# SCH_Knov-V3_3-sound-_DMS13A_2026-08-17.net
KiCad netlist of a schematic drawn in EasyEDA
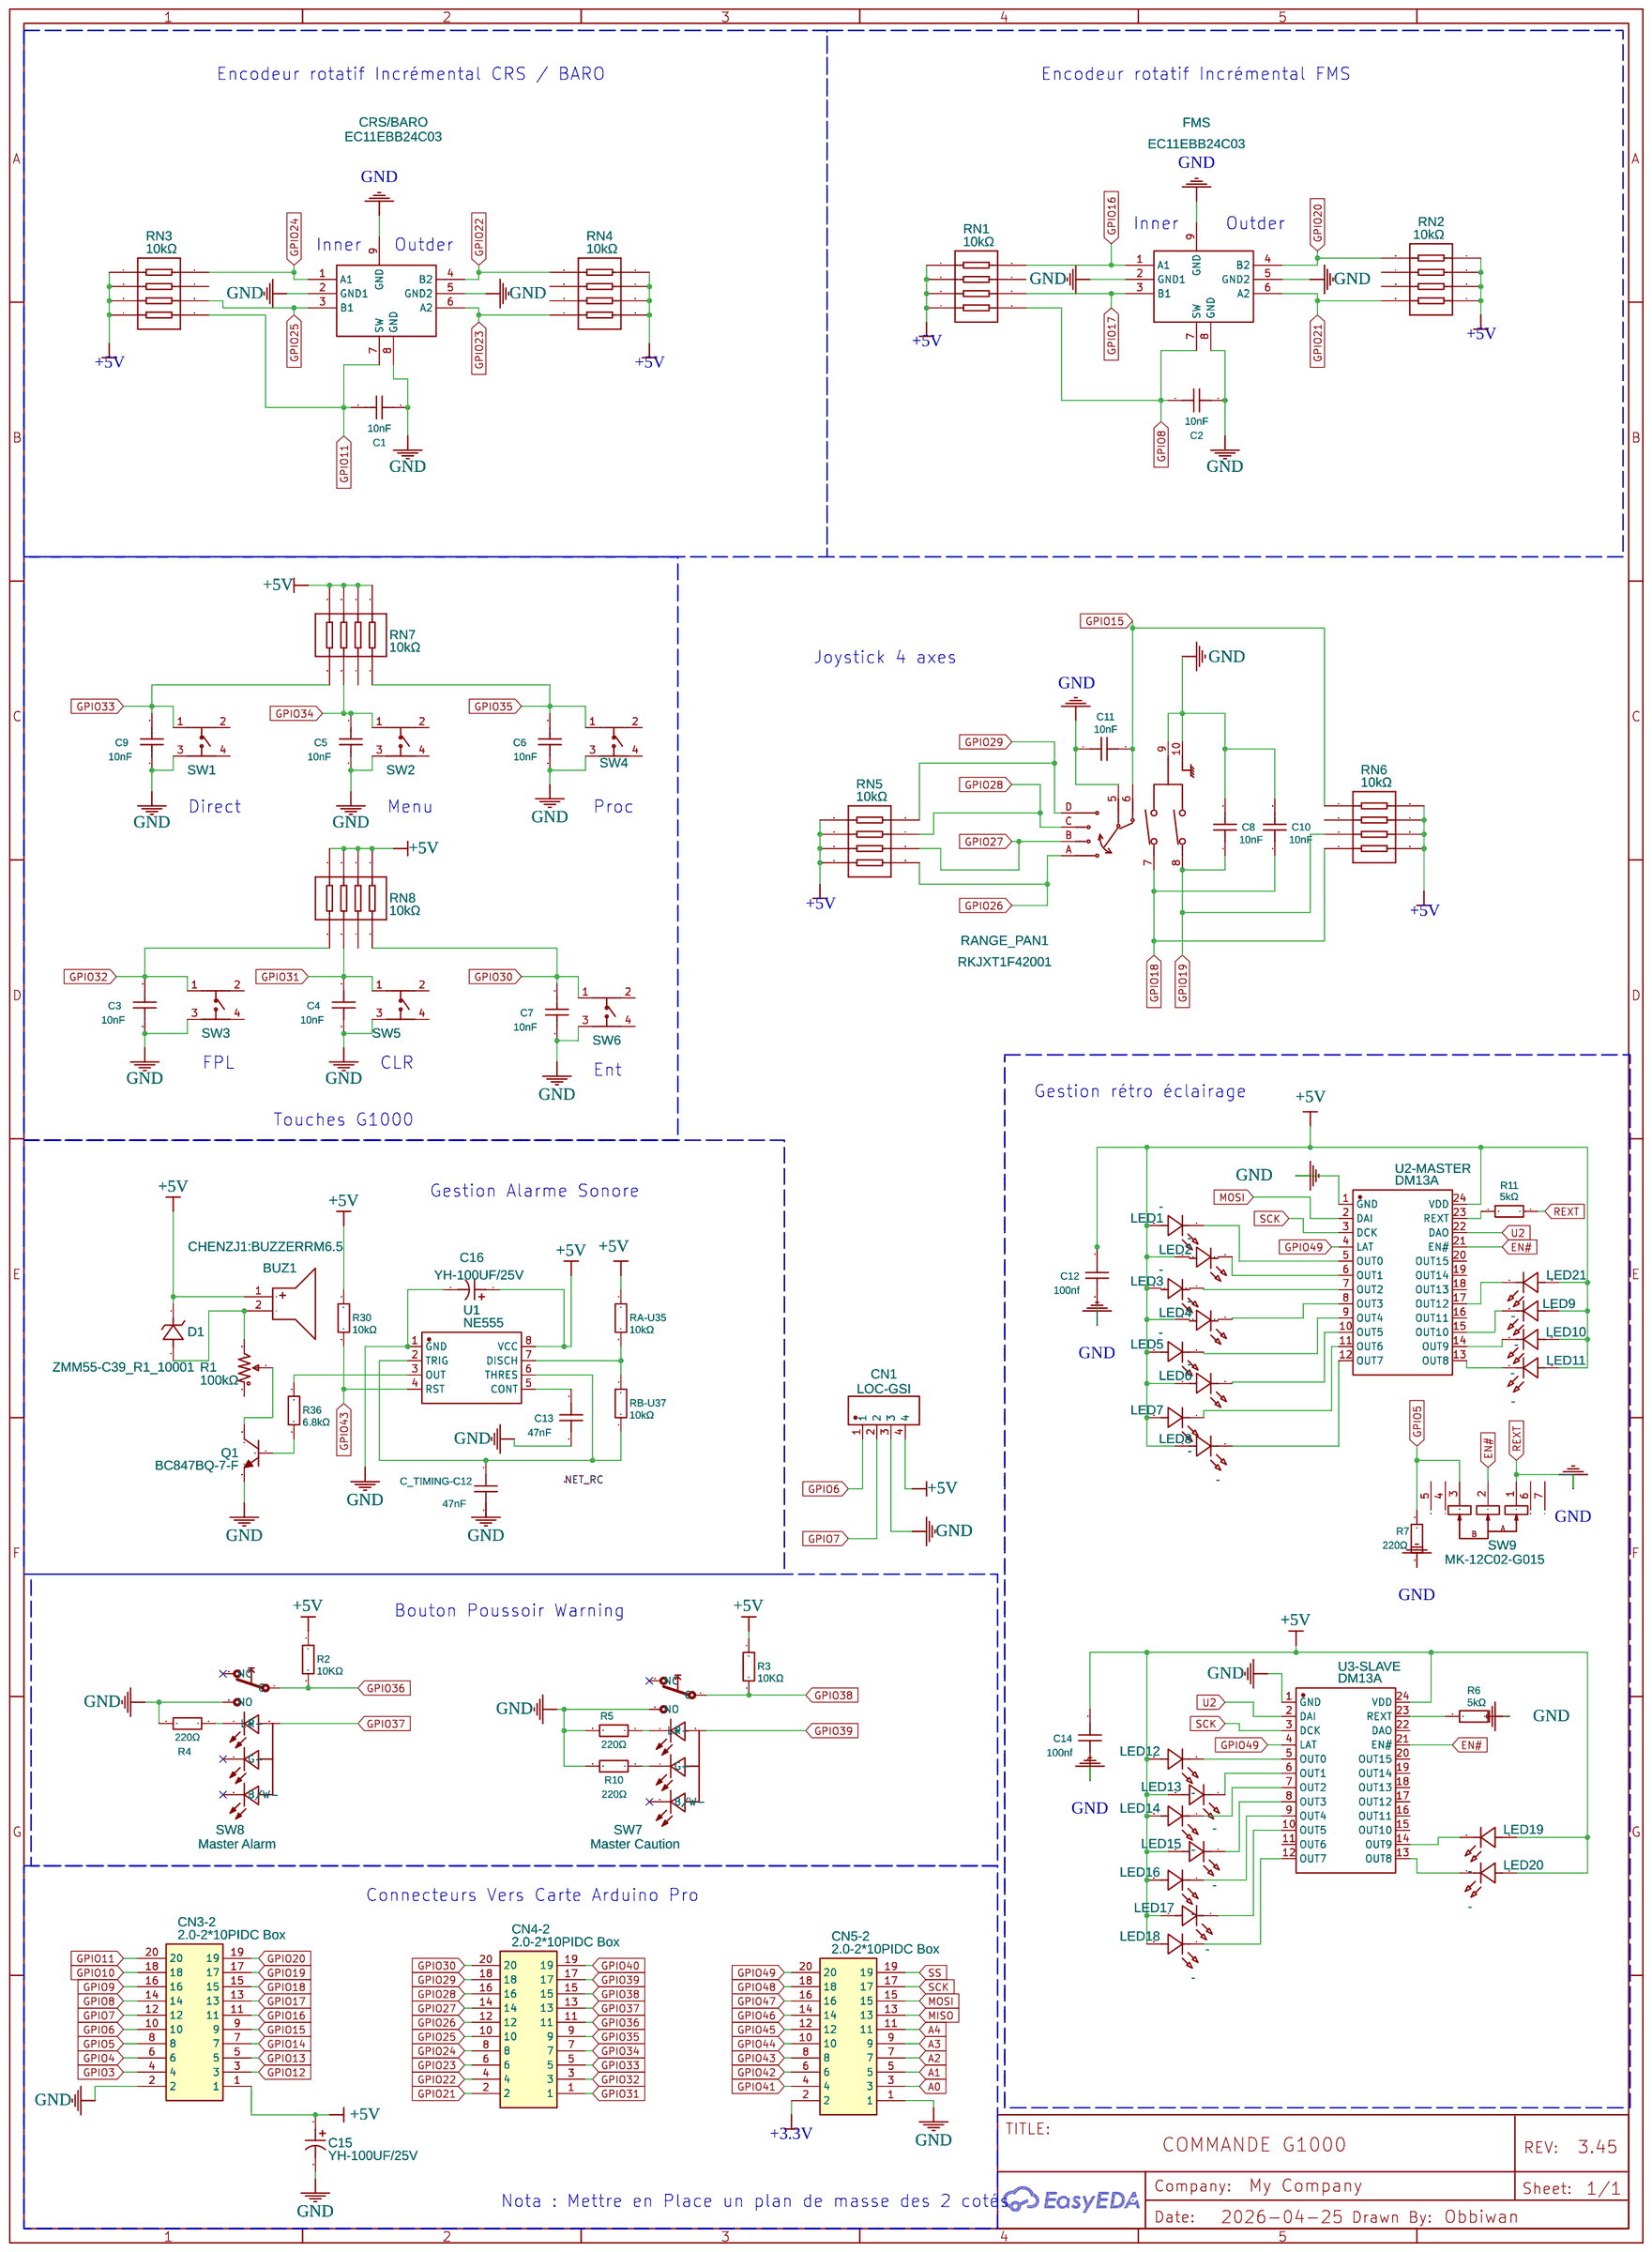
[diagram p0: Platine Bouton Sound +DMS13A]
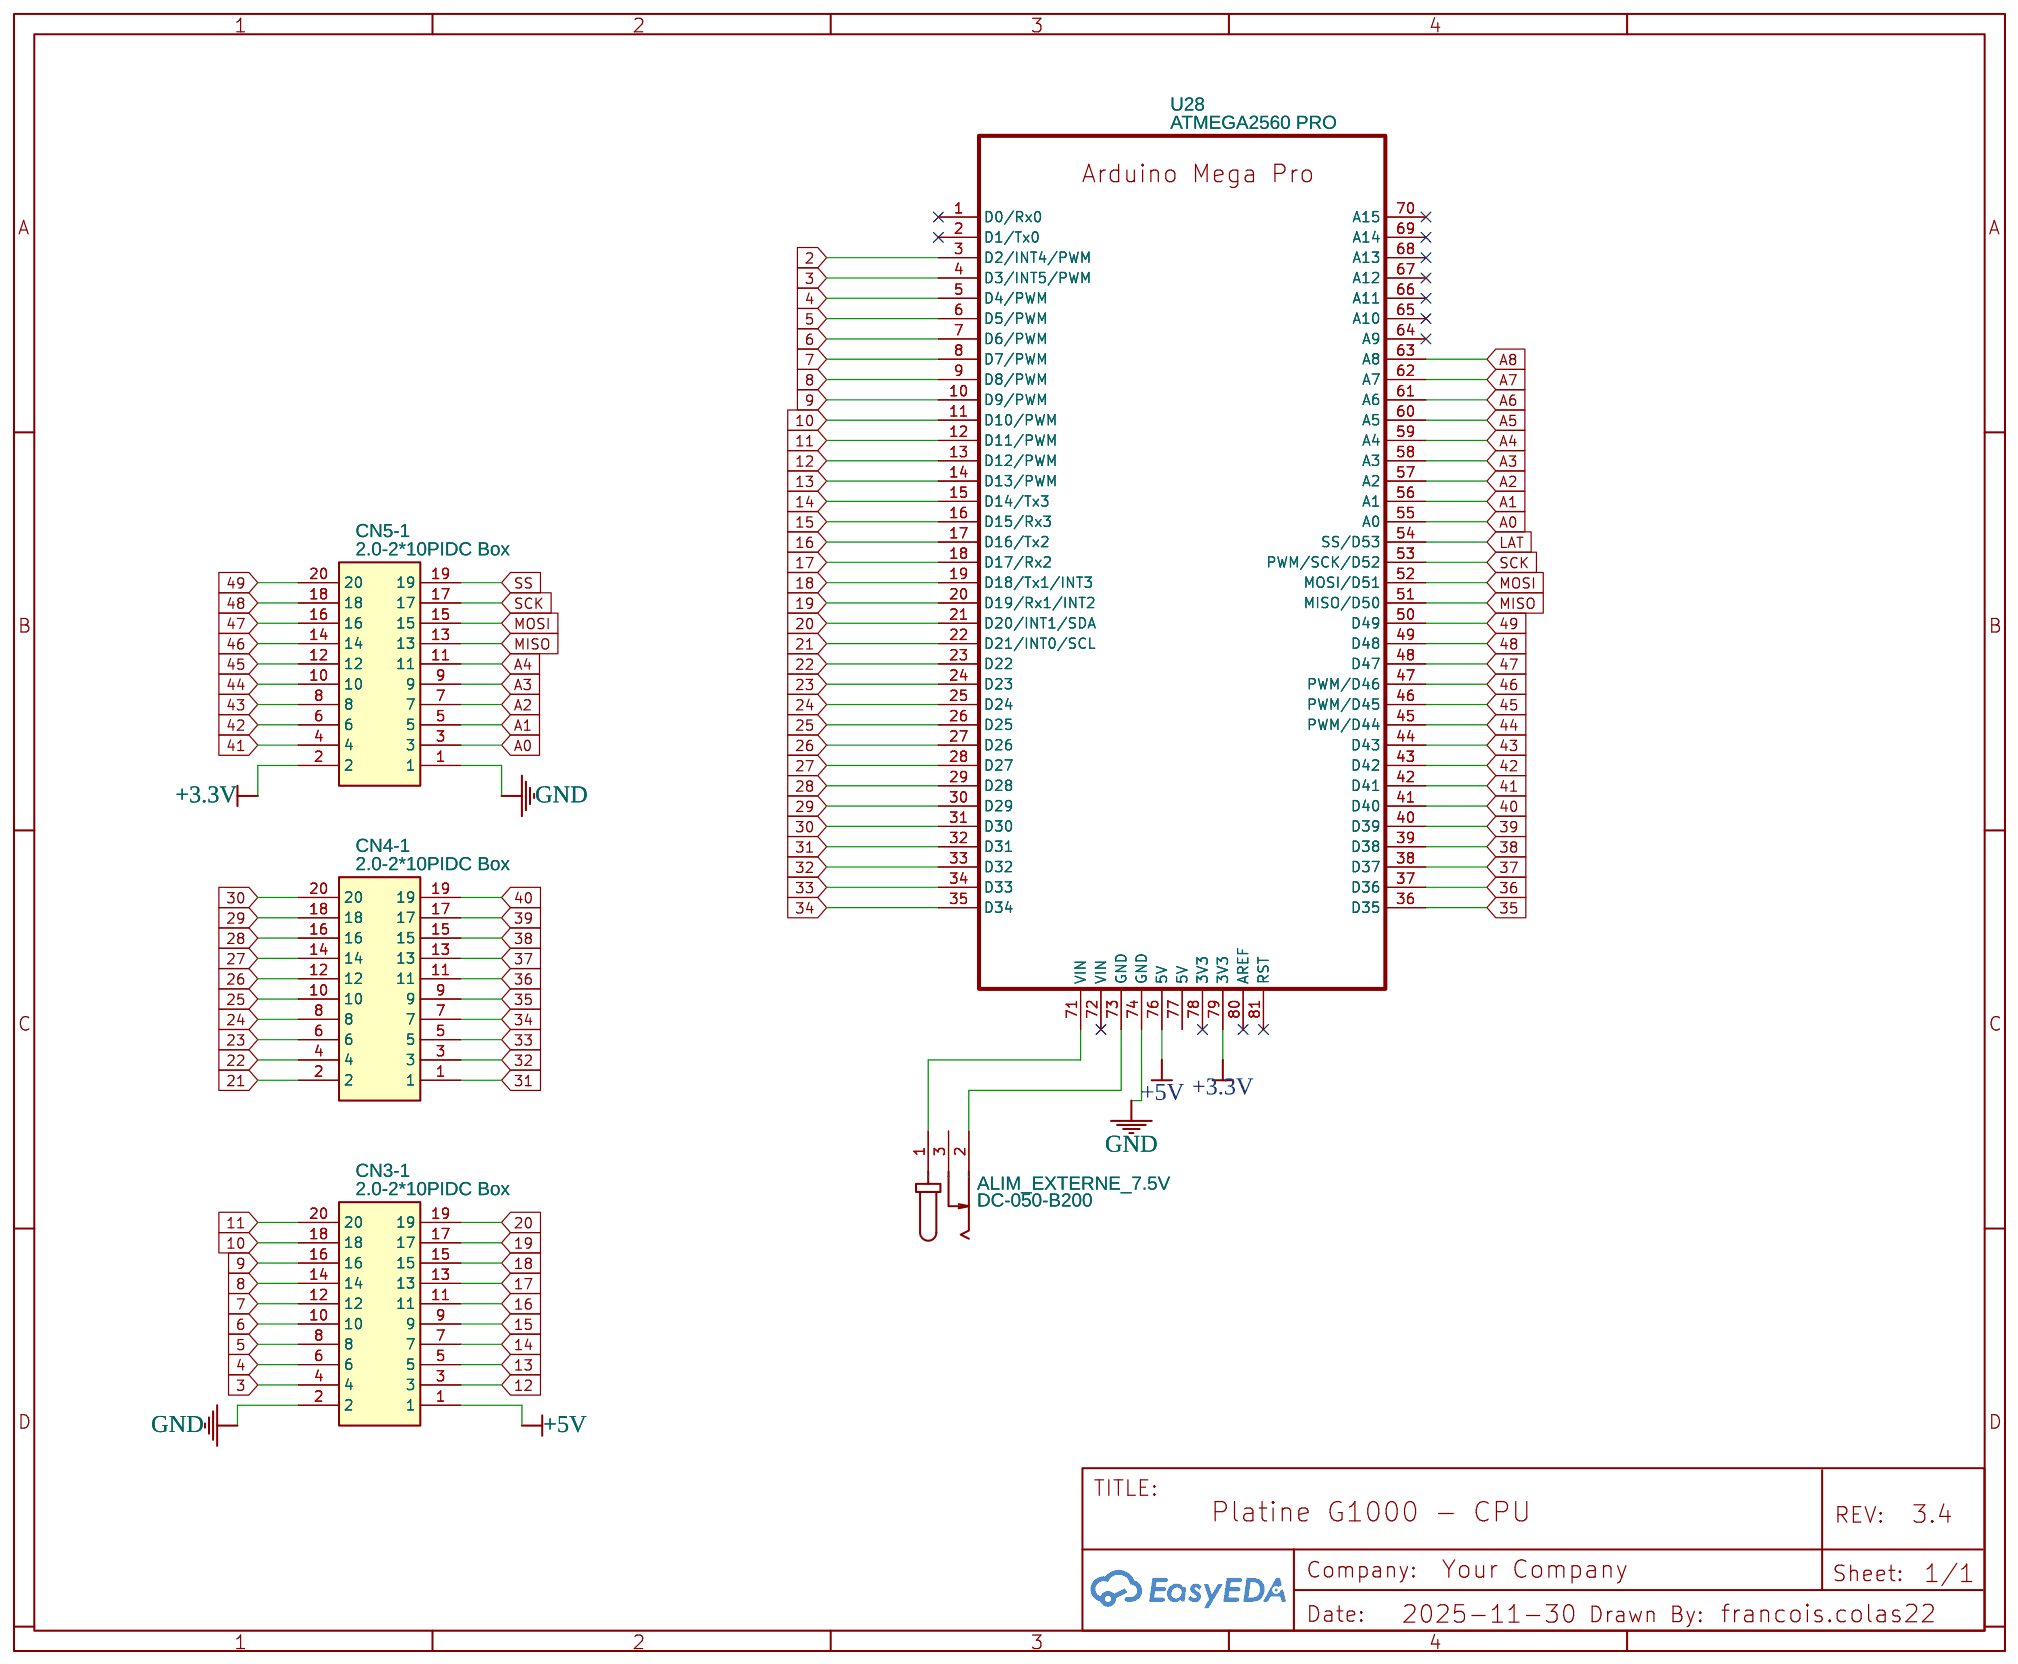
[diagram p1: Platine Arduino sound +DMS13A]
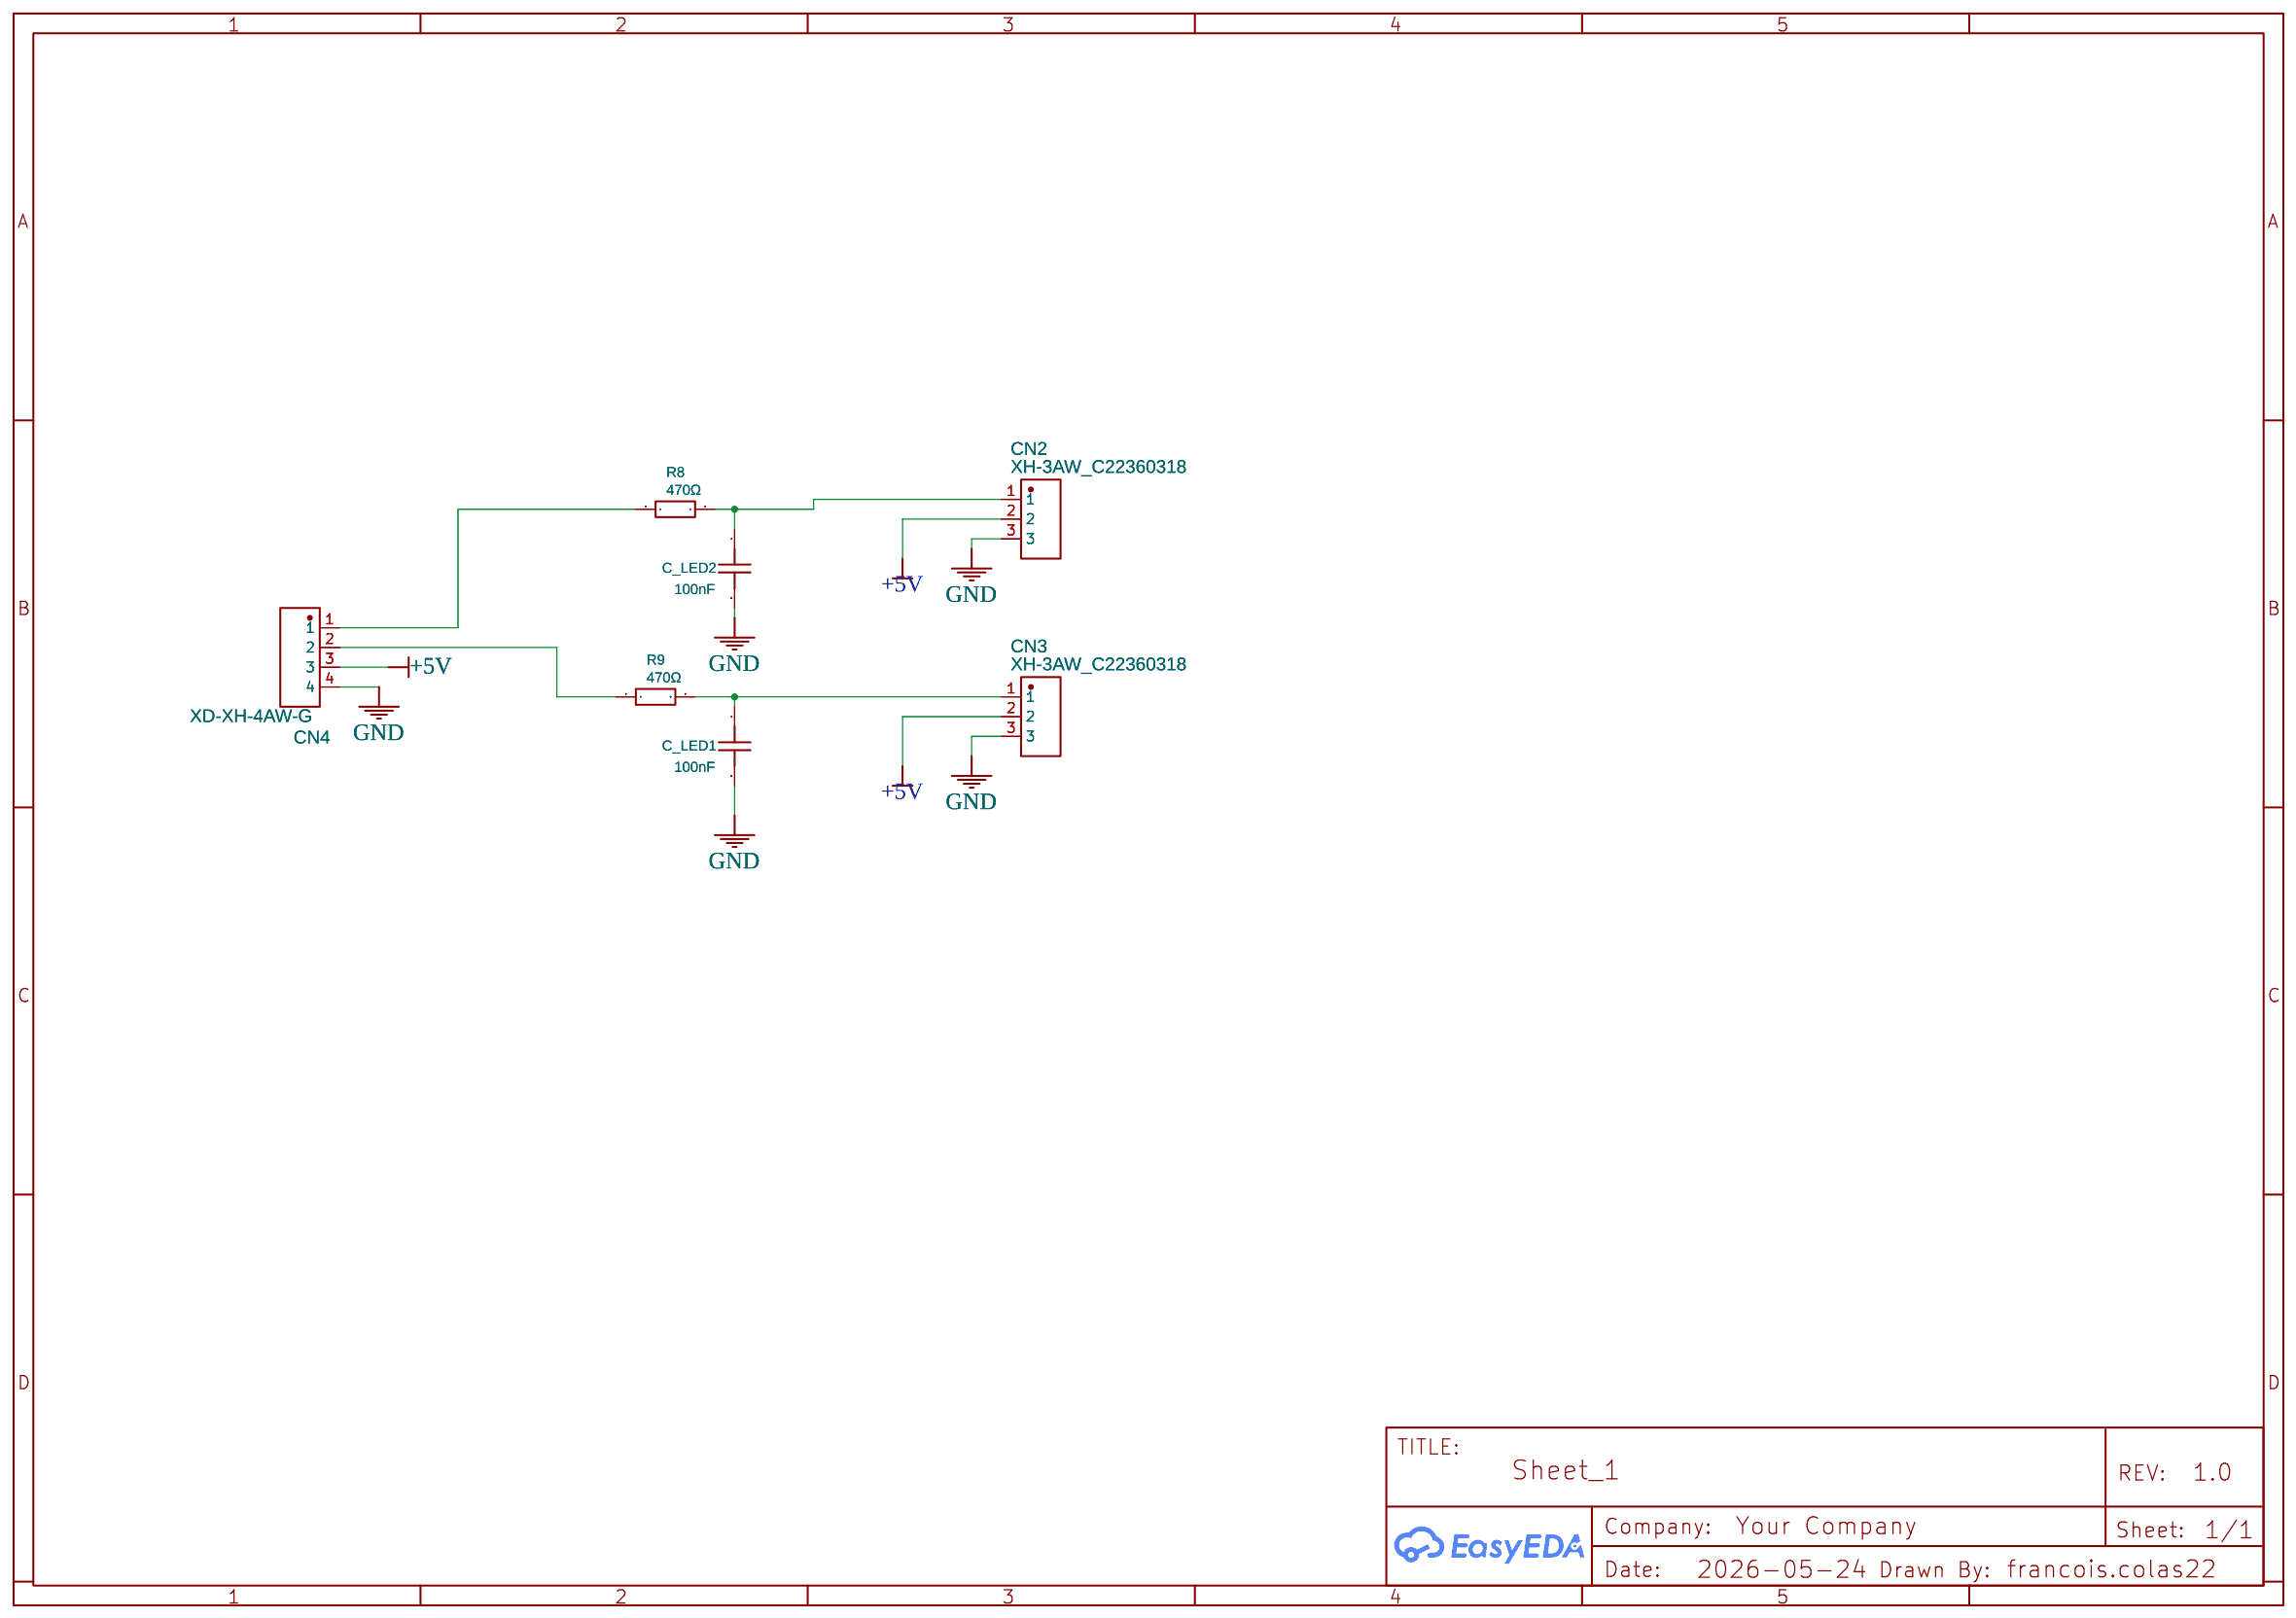
[diagram p2: Platine LED]

(export (version "E")
  (design (tool "Eeschema 10.0.6"))
  (components
    (comp (ref "BUZ1")
      (value "CHENZJ1:BUZZERRM6.5")
      (fields (field (name "Manufacturer Part") "chenzj1:Buzzer_12x9.5RM6.5"))
      (libsource (lib "") (part "CHENZJ1{colon}BUZZER_12X9.5RM6.5"))
    )
    (comp (ref "C1")
      (value "10nF")
      (fields
        (field (name "Manufacturer Part") "CT41G-0603-2X1-50V-0.01μF-K(N)")
        (field (name "Manufacturer") "TORCH(火炬)")
      )
      (libsource (lib "") (part "CT41G-0603-2X1-50V-0.01UF-K(N)"))
    )
    (comp (ref "C2")
      (value "10nF")
      (fields
        (field (name "Manufacturer Part") "CT41G-0603-2X1-50V-0.01μF-K(N)")
        (field (name "Manufacturer") "TORCH(火炬)")
      )
      (libsource (lib "") (part "CT41G-0603-2X1-50V-0.01UF-K(N)"))
    )
    (comp (ref "C3")
      (value "10nF")
      (fields
        (field (name "Manufacturer Part") "CT41G-0603-2X1-50V-0.01μF-K(N)")
        (field (name "Manufacturer") "TORCH(火炬)")
      )
      (libsource (lib "") (part "CT41G-0603-2X1-50V-0.01UF-K(N)_1"))
    )
    (comp (ref "C4")
      (value "10nF")
      (fields
        (field (name "Manufacturer Part") "CT41G-0603-2X1-50V-0.01μF-K(N)")
        (field (name "Manufacturer") "TORCH(火炬)")
      )
      (libsource (lib "") (part "CT41G-0603-2X1-50V-0.01UF-K(N)_1"))
    )
    (comp (ref "C5")
      (value "10nF")
      (fields
        (field (name "Manufacturer Part") "CT41G-0603-2X1-50V-0.01μF-K(N)")
        (field (name "Manufacturer") "TORCH(火炬)")
      )
      (libsource (lib "") (part "CT41G-0603-2X1-50V-0.01UF-K(N)_1"))
    )
    (comp (ref "C6")
      (value "10nF")
      (fields
        (field (name "Manufacturer Part") "CT41G-0603-2X1-50V-0.01μF-K(N)")
        (field (name "Manufacturer") "TORCH(火炬)")
      )
      (libsource (lib "") (part "CT41G-0603-2X1-50V-0.01UF-K(N)_1"))
    )
    (comp (ref "C7")
      (value "10nF")
      (fields
        (field (name "Manufacturer Part") "CT41G-0603-2X1-50V-0.01μF-K(N)")
        (field (name "Manufacturer") "TORCH(火炬)")
      )
      (libsource (lib "") (part "CT41G-0603-2X1-50V-0.01UF-K(N)_1"))
    )
    (comp (ref "C8")
      (value "10nF")
      (fields
        (field (name "Manufacturer Part") "CT41G-0603-2X1-50V-0.01μF-K(N)")
        (field (name "Manufacturer") "TORCH(火炬)")
      )
      (libsource (lib "") (part "CT41G-0603-2X1-50V-0.01UF-K(N)_2"))
    )
    (comp (ref "C9")
      (value "10nF")
      (fields
        (field (name "Manufacturer Part") "CT41G-0603-2X1-50V-0.01μF-K(N)")
        (field (name "Manufacturer") "TORCH(火炬)")
      )
      (libsource (lib "") (part "CT41G-0603-2X1-50V-0.01UF-K(N)_1"))
    )
    (comp (ref "C10")
      (value "10nF")
      (fields
        (field (name "Manufacturer Part") "CT41G-0603-2X1-50V-0.01μF-K(N)")
        (field (name "Manufacturer") "TORCH(火炬)")
      )
      (libsource (lib "") (part "CT41G-0603-2X1-50V-0.01UF-K(N)_2"))
    )
    (comp (ref "C11")
      (value "10nF")
      (fields
        (field (name "Manufacturer Part") "CT41G-0603-2X1-50V-0.01μF-K(N)")
        (field (name "Manufacturer") "TORCH(火炬)")
      )
      (libsource (lib "") (part "CT41G-0603-2X1-50V-0.01UF-K(N)"))
    )
    (comp (ref "C12")
      (value "100nf")
      (fields
        (field (name "Manufacturer Part") "CT41G-0603-2X1-50V-0.01μF-K(N)")
        (field (name "Manufacturer") "TORCH(火炬)")
      )
      (libsource (lib "") (part "CT41G-0603-2X1-50V-0.01UF-K(N)_1"))
    )
    (comp (ref "C13")
      (value "47nF")
      (fields
        (field (name "Manufacturer Part") "CT41G-0603-2X1-50V-0.01μF-K(N)")
        (field (name "Manufacturer") "TORCH(火炬)")
      )
      (libsource (lib "") (part "CT41G-0603-2X1-50V-0.01UF-K(N)_1"))
    )
    (comp (ref "C14")
      (value "100nf")
      (fields
        (field (name "Manufacturer Part") "CT41G-0603-2X1-50V-0.01μF-K(N)")
        (field (name "Manufacturer") "TORCH(火炬)")
      )
      (libsource (lib "") (part "CT41G-0603-2X1-50V-0.01UF-K(N)_1"))
    )
    (comp (ref "C15")
      (value "YH-100UF/25V")
      (fields (field (name "Manufacturer Part") "YH-100uF/25V-贴片电解电容"))
      (libsource (lib "") (part "YH-100UF/25V-贴片电解电容"))
    )
    (comp (ref "C16")
      (value "YH-100UF/25V")
      (fields (field (name "Manufacturer Part") "YH-100uF/25V-贴片电解电容"))
      (libsource (lib "") (part "YH-100UF/25V-贴片电解电容_1"))
    )
    (comp (ref "CN1")
      (value "LOC-GSI")
      (fields (field (name "Manufacturer Part") "XD-XH-4AW-G") (field (name "Manufacturer") "XUNDA(讯答)"))
      (libsource (lib "") (part "XD-XH-4AW-G"))
    )
    (comp (ref "CN3-2")
      (value "2.0-2*10PIDC Box")
      (fields (field (name "Manufacturer") "BOOMELE"))
      (libsource (lib "") (part "2.0-2*10PIDC Box_1"))
    )
    (comp (ref "CN4-2")
      (value "2.0-2*10PIDC Box")
      (fields (field (name "Manufacturer") "BOOMELE"))
      (libsource (lib "") (part "2.0-2*10PIDC Box"))
    )
    (comp (ref "CN5-2")
      (value "2.0-2*10PIDC Box")
      (fields (field (name "Manufacturer") "BOOMELE"))
      (libsource (lib "") (part "2.0-2*10PIDC Box_2"))
    )
    (comp (ref "CRS/BARO") (value "EC11EBB24C03") (libsource (lib "") (part "EC11EBB24C03")))
    (comp (ref "C_TIMING-C12")
      (value "47nF")
      (fields
        (field (name "Manufacturer Part") "CT41G-0603-2X1-50V-0.01μF-K(N)")
        (field (name "Manufacturer") "TORCH(火炬)")
      )
      (libsource (lib "") (part "CT41G-0603-2X1-50V-0.01UF-K(N)_3"))
    )
    (comp (ref "D1")
      (value "ZMM55-C39_R1_10001")
      (fields (field (name "Manufacturer") "PANJIT(强茂)"))
      (libsource (lib "") (part "ZMM55-C39_R1_10001"))
    )
    (comp (ref "FMS") (value "EC11EBB24C03") (libsource (lib "") (part "EC11EBB24C03_1")))
    (comp (ref "LED1")
      (value "-")
      (fields (field (name "Manufacturer Part") "YLED0805Y") (field (name "Manufacturer") "LITEON(光宝)"))
      (libsource (lib "") (part "TZ-P2-0805YTCS2-0.8T_2"))
    )
    (comp (ref "LED2")
      (value "-")
      (fields (field (name "Manufacturer Part") "YLED0805Y") (field (name "Manufacturer") "LITEON(光宝)"))
      (libsource (lib "") (part "TZ-P2-0805YTCS2-0.8T_5"))
    )
    (comp (ref "LED3")
      (value "-")
      (fields (field (name "Manufacturer Part") "YLED0805Y") (field (name "Manufacturer") "LITEON(光宝)"))
      (libsource (lib "") (part "TZ-P2-0805YTCS2-0.8T_6"))
    )
    (comp (ref "LED4")
      (value "-")
      (fields (field (name "Manufacturer Part") "YLED0805Y") (field (name "Manufacturer") "LITEON(光宝)"))
      (libsource (lib "") (part "TZ-P2-0805YTCS2-0.8T_8"))
    )
    (comp (ref "LED5")
      (value "-")
      (fields (field (name "Manufacturer Part") "YLED0805Y") (field (name "Manufacturer") "LITEON(光宝)"))
      (libsource (lib "") (part "TZ-P2-0805YTCS2-0.8T_7"))
    )
    (comp (ref "LED6")
      (value "-")
      (fields (field (name "Manufacturer Part") "YLED0805Y") (field (name "Manufacturer") "LITEON(光宝)"))
      (libsource (lib "") (part "TZ-P2-0805YTCS2-0.8T_4"))
    )
    (comp (ref "LED7")
      (value "-")
      (fields (field (name "Manufacturer Part") "YLED0805Y") (field (name "Manufacturer") "LITEON(光宝)"))
      (libsource (lib "") (part "TZ-P2-0805YTCS2-0.8T_9"))
    )
    (comp (ref "LED8")
      (value "-")
      (fields (field (name "Manufacturer Part") "YLED0805Y") (field (name "Manufacturer") "LITEON(光宝)"))
      (libsource (lib "") (part "TZ-P2-0805YTCS2-0.8T_2"))
    )
    (comp (ref "LED9")
      (value "-")
      (fields (field (name "Manufacturer Part") "YLED0805Y") (field (name "Manufacturer") "LITEON(光宝)"))
      (libsource (lib "") (part "TZ-P2-0805YTCS2-0.8T_1"))
    )
    (comp (ref "LED10")
      (value "-")
      (fields (field (name "Manufacturer Part") "YLED0805Y") (field (name "Manufacturer") "LITEON(光宝)"))
      (libsource (lib "") (part "TZ-P2-0805YTCS2-0.8T_1"))
    )
    (comp (ref "LED11")
      (value "-")
      (fields (field (name "Manufacturer Part") "YLED0805Y") (field (name "Manufacturer") "LITEON(光宝)"))
      (libsource (lib "") (part "TZ-P2-0805YTCS2-0.8T_1"))
    )
    (comp (ref "LED12")
      (value "-")
      (fields (field (name "Manufacturer Part") "YLED0805Y") (field (name "Manufacturer") "LITEON(光宝)"))
      (libsource (lib "") (part "TZ-P2-0805YTCS2-0.8T_2"))
    )
    (comp (ref "LED13")
      (value "-")
      (fields (field (name "Manufacturer Part") "YLED0805Y") (field (name "Manufacturer") "LITEON(光宝)"))
      (libsource (lib "") (part "TZ-P2-0805YTCS2-0.8T_3"))
    )
    (comp (ref "LED14")
      (value "-")
      (fields (field (name "Manufacturer Part") "YLED0805Y") (field (name "Manufacturer") "LITEON(光宝)"))
      (libsource (lib "") (part "TZ-P2-0805YTCS2-0.8T"))
    )
    (comp (ref "LED15")
      (value "-")
      (fields (field (name "Manufacturer Part") "YLED0805Y") (field (name "Manufacturer") "LITEON(光宝)"))
      (libsource (lib "") (part "TZ-P2-0805YTCS2-0.8T"))
    )
    (comp (ref "LED16")
      (value "-")
      (fields (field (name "Manufacturer Part") "YLED0805Y") (field (name "Manufacturer") "LITEON(光宝)"))
      (libsource (lib "") (part "TZ-P2-0805YTCS2-0.8T_3"))
    )
    (comp (ref "LED17")
      (value "-")
      (fields (field (name "Manufacturer Part") "YLED0805Y") (field (name "Manufacturer") "LITEON(光宝)"))
      (libsource (lib "") (part "TZ-P2-0805YTCS2-0.8T_3"))
    )
    (comp (ref "LED18")
      (value "-")
      (fields (field (name "Manufacturer Part") "YLED0805Y") (field (name "Manufacturer") "LITEON(光宝)"))
      (libsource (lib "") (part "TZ-P2-0805YTCS2-0.8T"))
    )
    (comp (ref "LED19")
      (value "-")
      (fields (field (name "Manufacturer Part") "YLED0805Y") (field (name "Manufacturer") "LITEON(光宝)"))
      (libsource (lib "") (part "TZ-P2-0805YTCS2-0.8T_1"))
    )
    (comp (ref "LED20")
      (value "-")
      (fields (field (name "Manufacturer Part") "YLED0805Y") (field (name "Manufacturer") "LITEON(光宝)"))
      (libsource (lib "") (part "TZ-P2-0805YTCS2-0.8T_1"))
    )
    (comp (ref "LED21")
      (value "-")
      (fields (field (name "Manufacturer Part") "YLED0805Y") (field (name "Manufacturer") "LITEON(光宝)"))
      (libsource (lib "") (part "TZ-P2-0805YTCS2-0.8T_1"))
    )
    (comp (ref "Q1")
      (value "BC847BQ-7-F")
      (fields (field (name "Manufacturer") "DIODES(美台)"))
      (libsource (lib "") (part "BC847BQ-7-F"))
    )
    (comp (ref "R1")
      (value "100kΩ")
      (fields (field (name "Manufacturer Part") "RM065-204(200K)") (field (name "Manufacturer") "BOCHEN(博晨)"))
      (libsource (lib "") (part "RM065-204(200K)"))
    )
    (comp (ref "R2")
      (value "10KΩ")
      (fields (field (name "Manufacturer Part") "SCR0603J10K") (field (name "Manufacturer") "RESI(开步睿思）"))
      (libsource (lib "") (part "HPCR0603F5K60K9_1"))
    )
    (comp (ref "R3")
      (value "10KΩ")
      (fields (field (name "Manufacturer Part") "SCR0603J10K") (field (name "Manufacturer") "RESI(开步睿思）"))
      (libsource (lib "") (part "HPCR0603F5K60K9_1"))
    )
    (comp (ref "R4")
      (value "220Ω")
      (fields (field (name "Manufacturer Part") "HPCR0603F5K60K9") (field (name "Manufacturer") "RESI(开步睿思）"))
      (libsource (lib "") (part "HPCR0603F5K60K9"))
    )
    (comp (ref "R5")
      (value "220Ω")
      (fields (field (name "Manufacturer Part") "HPCR0603F5K60K9") (field (name "Manufacturer") "RESI(开步睿思）"))
      (libsource (lib "") (part "HPCR0603F5K60K9"))
    )
    (comp (ref "R6")
      (value "5kΩ")
      (fields (field (name "Manufacturer Part") "HPCR0603F5K60K9") (field (name "Manufacturer") "RESI(开步睿思）"))
      (libsource (lib "") (part "HPCR0603F5K60K9"))
    )
    (comp (ref "R7")
      (value "220Ω")
      (fields (field (name "Manufacturer Part") "SCR0603J10K") (field (name "Manufacturer") "RESI(开步睿思）"))
      (libsource (lib "") (part "HPCR0603F5K60K9_1"))
    )
    (comp (ref "R10")
      (value "220Ω")
      (fields (field (name "Manufacturer Part") "HPCR0603F5K60K9") (field (name "Manufacturer") "RESI(开步睿思）"))
      (libsource (lib "") (part "HPCR0603F5K60K9"))
    )
    (comp (ref "R11")
      (value "5kΩ")
      (fields (field (name "Manufacturer Part") "HPCR0603F5K60K9") (field (name "Manufacturer") "RESI(开步睿思）"))
      (libsource (lib "") (part "HPCR0603F5K60K9"))
    )
    (comp (ref "R30")
      (value "10kΩ")
      (fields (field (name "Manufacturer Part") "SCR0603J10K") (field (name "Manufacturer") "RESI(开步睿思）"))
      (libsource (lib "") (part "HPCR0603F5K60K9_1"))
    )
    (comp (ref "R36")
      (value "6.8kΩ")
      (fields (field (name "Manufacturer Part") "SCR0603J10K") (field (name "Manufacturer") "RESI(开步睿思）"))
      (libsource (lib "") (part "HPCR0603F5K60K9_4"))
    )
    (comp (ref "RA-U35")
      (value "10kΩ")
      (fields (field (name "Manufacturer Part") "SCR0603J10K") (field (name "Manufacturer") "RESI(开步睿思）"))
      (libsource (lib "") (part "HPCR0603F5K60K9_3"))
    )
    (comp (ref "RANGE_PAN1")
      (value "RKJXT1F42001")
      (fields (field (name "Manufacturer") "ALPSALPINE(阿尔卑斯阿尔派)"))
      (libsource (lib "") (part "RKJXT1F42001"))
    )
    (comp (ref "RB-U37")
      (value "10kΩ")
      (fields (field (name "Manufacturer Part") "SCR0603J10K") (field (name "Manufacturer") "RESI(开步睿思）"))
      (libsource (lib "") (part "HPCR0603F5K60K9_2"))
    )
    (comp (ref "RN1")
      (value "10kΩ")
      (fields (field (name "Manufacturer Part") "RTA03-4D103JTP") (field (name "Manufacturer") "RALEC(旺诠)"))
      (libsource (lib "") (part "RTA03-4D103JTP_1"))
    )
    (comp (ref "RN2")
      (value "10kΩ")
      (fields (field (name "Manufacturer Part") "RTA03-4D103JTP") (field (name "Manufacturer") "RALEC(旺诠)"))
      (libsource (lib "") (part "RTA03-4D103JTP_2"))
    )
    (comp (ref "RN3")
      (value "10kΩ")
      (fields (field (name "Manufacturer Part") "RTA03-4D103JTP") (field (name "Manufacturer") "RALEC(旺诠)"))
      (libsource (lib "") (part "RTA03-4D103JTP_1"))
    )
    (comp (ref "RN4")
      (value "10kΩ")
      (fields (field (name "Manufacturer Part") "RTA03-4D103JTP") (field (name "Manufacturer") "RALEC(旺诠)"))
      (libsource (lib "") (part "RTA03-4D103JTP_1"))
    )
    (comp (ref "RN5")
      (value "10kΩ")
      (fields (field (name "Manufacturer Part") "RTA03-4D103JTP") (field (name "Manufacturer") "RALEC(旺诠)"))
      (libsource (lib "") (part "RTA03-4D103JTP_1"))
    )
    (comp (ref "RN6")
      (value "10kΩ")
      (fields (field (name "Manufacturer Part") "RTA03-4D103JTP") (field (name "Manufacturer") "RALEC(旺诠)"))
      (libsource (lib "") (part "RTA03-4D103JTP_1"))
    )
    (comp (ref "RN7")
      (value "10kΩ")
      (fields (field (name "Manufacturer Part") "RTA03-4D103JTP") (field (name "Manufacturer") "RALEC(旺诠)"))
      (libsource (lib "") (part "RTA03-4D103JTP"))
    )
    (comp (ref "RN8")
      (value "10kΩ")
      (fields (field (name "Manufacturer Part") "RTA03-4D103JTP") (field (name "Manufacturer") "RALEC(旺诠)"))
      (libsource (lib "") (part "RTA03-4D103JTP"))
    )
    (comp (ref "SW1")
      (value "YTS-D001-285")
      (fields (field (name "Manufacturer") "YIYUAN(怡远)"))
      (libsource (lib "") (part "YTS-D001-285"))
    )
    (comp (ref "SW2")
      (value "YTS-D001-285")
      (fields (field (name "Manufacturer") "YIYUAN(怡远)"))
      (libsource (lib "") (part "YTS-D001-285"))
    )
    (comp (ref "SW3")
      (value "YTS-D001-285")
      (fields (field (name "Manufacturer") "YIYUAN(怡远)"))
      (libsource (lib "") (part "YTS-D001-285"))
    )
    (comp (ref "SW4")
      (value "YTS-D001-285")
      (fields (field (name "Manufacturer") "YIYUAN(怡远)"))
      (libsource (lib "") (part "YTS-D001-285"))
    )
    (comp (ref "SW5")
      (value "YTS-D001-285")
      (fields (field (name "Manufacturer") "YIYUAN(怡远)"))
      (libsource (lib "") (part "YTS-D001-285"))
    )
    (comp (ref "SW6")
      (value "YTS-D001-285")
      (fields (field (name "Manufacturer") "YIYUAN(怡远)"))
      (libsource (lib "") (part "YTS-D001-285"))
    )
    (comp (ref "SW7")
      (value "Master Caution")
      (fields (field (name "Manufacturer Part") "PB26-13M RGB/W") (field (name "Manufacturer") "Honyone"))
      (libsource (lib "") (part "PB26-13M RGB/W"))
    )
    (comp (ref "SW8")
      (value "Master Alarm")
      (fields (field (name "Manufacturer Part") "PB26-13M RGB/W") (field (name "Manufacturer") "Honyone"))
      (libsource (lib "") (part "PB26-13M RGB/W"))
    )
    (comp (ref "SW9")
      (value "MK-12C02-G015")
      (fields (field (name "Manufacturer") "G-Switch(品赞)"))
      (libsource (lib "") (part "MK-12C02-G015"))
    )
    (comp (ref "U1")
      (value "NE555")
      (fields (field (name "Manufacturer Part") "NE555DR") (field (name "Manufacturer") "TECH PUBLIC(台舟)"))
      (libsource (lib "") (part "NE555DR_C41431778"))
    )
    (comp (ref "U2-MASTER") (value "DM13A") (libsource (lib "") (part "DM13A")))
    (comp (ref "U3-SLAVE") (value "DM13A") (libsource (lib "") (part "DM13A_1")))
    (comp (ref "ALIM_EXTERNE_7.5V")
      (value "DC-050-B200")
      (fields (field (name "Manufacturer") "XUNPU(讯普)"))
      (libsource (lib "") (part "DC-050-B200"))
    )
    (comp (ref "CN3-1")
      (value "2.0-2*10PIDC Box")
      (fields (field (name "Manufacturer") "BOOMELE"))
      (libsource (lib "") (part "2.0-2*10PIDC Box"))
    )
    (comp (ref "CN4-1")
      (value "2.0-2*10PIDC Box")
      (fields (field (name "Manufacturer") "BOOMELE"))
      (libsource (lib "") (part "2.0-2*10PIDC Box_1"))
    )
    (comp (ref "CN5-1")
      (value "2.0-2*10PIDC Box")
      (fields (field (name "Manufacturer") "BOOMELE"))
      (libsource (lib "") (part "2.0-2*10PIDC Box_2"))
    )
    (comp (ref "U28")
      (value "ATMEGA2560 PRO")
      (fields
        (field (name "Manufacturer Part") "MEGA-PRO-CH340G/ATmega2560")
        (field (name "Manufacturer") "RobotDyn")
      )
      (libsource (lib "") (part "ATMEGA2560 PRO"))
    )
    (comp (ref "CN2")
      (value "XH-3AW_C22360318")
      (fields (field (name "Manufacturer Part") "XH-3AW") (field (name "Manufacturer") "韩国韩荣"))
      (libsource (lib "") (part "XH-3AW_C22360318"))
    )
    (comp (ref "CN3")
      (value "XH-3AW_C22360318")
      (fields (field (name "Manufacturer Part") "XH-3AW") (field (name "Manufacturer") "韩国韩荣"))
      (libsource (lib "") (part "XH-3AW_C22360318"))
    )
    (comp (ref "CN4")
      (value "XD-XH-4AW-G")
      (fields (field (name "Manufacturer") "XUNDA(讯答)"))
      (libsource (lib "") (part "XD-XH-4AW-G"))
    )
    (comp (ref "C_LED1")
      (value "100nF")
      (fields
        (field (name "Manufacturer Part") "CT41G-0603-2X1-50V-0.01μF-K(N)")
        (field (name "Manufacturer") "TORCH(火炬)")
      )
      (libsource (lib "") (part "CT41G-0603-2X1-50V-0.01UF-K(N)"))
    )
    (comp (ref "C_LED2")
      (value "100nF")
      (fields
        (field (name "Manufacturer Part") "CT41G-0603-2X1-50V-0.01μF-K(N)")
        (field (name "Manufacturer") "TORCH(火炬)")
      )
      (libsource (lib "") (part "CT41G-0603-2X1-50V-0.01UF-K(N)"))
    )
    (comp (ref "R8")
      (value "470Ω")
      (fields (field (name "Manufacturer Part") "SCR0603J10K") (field (name "Manufacturer") "RESI(开步睿思）"))
      (libsource (lib "") (part "HPCR0603F5K60K9"))
    )
    (comp (ref "R9")
      (value "470Ω")
      (fields (field (name "Manufacturer Part") "SCR0603J10K") (field (name "Manufacturer") "RESI(开步睿思）"))
      (libsource (lib "") (part "HPCR0603F5K60K9"))
    )
  )
  (nets
    (net (code "1") (name "+3.3V") (class "Default")
      (node (ref "CN5-1") (pin "2") (pinfunction "2_2") (pintype "unspecified"))
      (node (ref "CN5-2") (pin "2") (pinfunction "2_2") (pintype "unspecified"))
      (node (ref "U28") (pin "79") (pinfunction "3V3_79") (pintype "unspecified"))
    )
    (net (code "2") (name "+5V") (class "Default")
      (node (ref "BUZ1") (pin "1") (pinfunction "+_1") (pintype "unspecified"))
      (node (ref "C12") (pin "1") (pinfunction "1_1") (pintype "unspecified"))
      (node (ref "C14") (pin "1") (pinfunction "1_1") (pintype "unspecified"))
      (node (ref "C15") (pin "1") (pinfunction "1_1") (pintype "input"))
      (node (ref "C16") (pin "1") (pinfunction "1_1") (pintype "input"))
      (node (ref "CN1") (pin "4") (pinfunction "4_4") (pintype "unspecified"))
      (node (ref "CN2") (pin "2") (pinfunction "2_2") (pintype "unspecified"))
      (node (ref "CN3") (pin "2") (pinfunction "2_2") (pintype "unspecified"))
      (node (ref "CN3-1") (pin "1") (pinfunction "1_1") (pintype "unspecified"))
      (node (ref "CN3-2") (pin "1") (pinfunction "1_1") (pintype "unspecified"))
      (node (ref "CN4") (pin "3") (pinfunction "3_3") (pintype "unspecified"))
      (node (ref "D1") (pin "1") (pinfunction "K_1") (pintype "unspecified"))
      (node (ref "LED1") (pin "2") (pinfunction "A_2") (pintype "unspecified"))
      (node (ref "LED10") (pin "2") (pinfunction "A_2") (pintype "unspecified"))
      (node (ref "LED11") (pin "2") (pinfunction "A_2") (pintype "unspecified"))
      (node (ref "LED12") (pin "2") (pinfunction "A_2") (pintype "unspecified"))
      (node (ref "LED13") (pin "2") (pinfunction "A_2") (pintype "unspecified"))
      (node (ref "LED14") (pin "2") (pinfunction "A_2") (pintype "unspecified"))
      (node (ref "LED15") (pin "2") (pinfunction "A_2") (pintype "unspecified"))
      (node (ref "LED16") (pin "2") (pinfunction "A_2") (pintype "unspecified"))
      (node (ref "LED17") (pin "2") (pinfunction "A_2") (pintype "unspecified"))
      (node (ref "LED18") (pin "2") (pinfunction "A_2") (pintype "unspecified"))
      (node (ref "LED19") (pin "2") (pinfunction "A_2") (pintype "unspecified"))
      (node (ref "LED2") (pin "2") (pinfunction "A_2") (pintype "unspecified"))
      (node (ref "LED20") (pin "2") (pinfunction "A_2") (pintype "unspecified"))
      (node (ref "LED21") (pin "2") (pinfunction "A_2") (pintype "unspecified"))
      (node (ref "LED3") (pin "2") (pinfunction "A_2") (pintype "unspecified"))
      (node (ref "LED4") (pin "2") (pinfunction "A_2") (pintype "unspecified"))
      (node (ref "LED5") (pin "2") (pinfunction "A_2") (pintype "unspecified"))
      (node (ref "LED6") (pin "2") (pinfunction "A_2") (pintype "unspecified"))
      (node (ref "LED7") (pin "2") (pinfunction "A_2") (pintype "unspecified"))
      (node (ref "LED8") (pin "2") (pinfunction "A_2") (pintype "unspecified"))
      (node (ref "LED9") (pin "2") (pinfunction "A_2") (pintype "unspecified"))
      (node (ref "R2") (pin "1") (pinfunction "1_1") (pintype "unspecified"))
      (node (ref "R3") (pin "1") (pinfunction "1_1") (pintype "unspecified"))
      (node (ref "R30") (pin "1") (pinfunction "1_1") (pintype "unspecified"))
      (node (ref "RA-U35") (pin "1") (pinfunction "1_1") (pintype "unspecified"))
      (node (ref "RN1") (pin "1") (pinfunction "1_1") (pintype "input"))
      (node (ref "RN1") (pin "2") (pinfunction "2_2") (pintype "input"))
      (node (ref "RN1") (pin "3") (pinfunction "3_3") (pintype "input"))
      (node (ref "RN1") (pin "4") (pinfunction "4_4") (pintype "input"))
      (node (ref "RN2") (pin "1") (pinfunction "1_1") (pintype "input"))
      (node (ref "RN2") (pin "2") (pinfunction "2_2") (pintype "input"))
      (node (ref "RN2") (pin "3") (pinfunction "3_3") (pintype "input"))
      (node (ref "RN2") (pin "4") (pinfunction "4_4") (pintype "input"))
      (node (ref "RN3") (pin "1") (pinfunction "1_1") (pintype "input"))
      (node (ref "RN3") (pin "2") (pinfunction "2_2") (pintype "input"))
      (node (ref "RN3") (pin "3") (pinfunction "3_3") (pintype "input"))
      (node (ref "RN3") (pin "4") (pinfunction "4_4") (pintype "input"))
      (node (ref "RN4") (pin "5") (pinfunction "5_5") (pintype "input"))
      (node (ref "RN4") (pin "6") (pinfunction "6_6") (pintype "input"))
      (node (ref "RN4") (pin "7") (pinfunction "7_7") (pintype "input"))
      (node (ref "RN4") (pin "8") (pinfunction "8_8") (pintype "input"))
      (node (ref "RN5") (pin "1") (pinfunction "1_1") (pintype "input"))
      (node (ref "RN5") (pin "2") (pinfunction "2_2") (pintype "input"))
      (node (ref "RN5") (pin "3") (pinfunction "3_3") (pintype "input"))
      (node (ref "RN5") (pin "4") (pinfunction "4_4") (pintype "input"))
      (node (ref "RN6") (pin "5") (pinfunction "5_5") (pintype "input"))
      (node (ref "RN6") (pin "6") (pinfunction "6_6") (pintype "input"))
      (node (ref "RN6") (pin "7") (pinfunction "7_7") (pintype "input"))
      (node (ref "RN6") (pin "8") (pinfunction "8_8") (pintype "input"))
      (node (ref "RN7") (pin "1") (pinfunction "1_1") (pintype "input"))
      (node (ref "RN7") (pin "2") (pinfunction "2_2") (pintype "input"))
      (node (ref "RN7") (pin "3") (pinfunction "3_3") (pintype "input"))
      (node (ref "RN7") (pin "4") (pinfunction "4_4") (pintype "input"))
      (node (ref "RN8") (pin "1") (pinfunction "1_1") (pintype "input"))
      (node (ref "RN8") (pin "2") (pinfunction "2_2") (pintype "input"))
      (node (ref "RN8") (pin "3") (pinfunction "3_3") (pintype "input"))
      (node (ref "RN8") (pin "4") (pinfunction "4_4") (pintype "input"))
      (node (ref "U1") (pin "8") (pinfunction "VCC_8") (pintype "unspecified"))
      (node (ref "U2-MASTER") (pin "24") (pinfunction "VDD_24") (pintype "unspecified"))
      (node (ref "U28") (pin "76") (pinfunction "5V_76") (pintype "unspecified"))
      (node (ref "U3-SLAVE") (pin "24") (pinfunction "VDD_24") (pintype "unspecified"))
    )
    (net (code "3") (name "2") (class "Default")
      (node (ref "U28") (pin "3") (pinfunction "D2/INT4/PWM_3") (pintype "unspecified"))
    )
    (net (code "4") (name "3") (class "Default")
      (node (ref "CN3-1") (pin "4") (pinfunction "4_4") (pintype "unspecified"))
      (node (ref "U28") (pin "4") (pinfunction "D3/INT5/PWM_4") (pintype "unspecified"))
    )
    (net (code "5") (name "4") (class "Default")
      (node (ref "CN3-1") (pin "6") (pinfunction "6_6") (pintype "unspecified"))
      (node (ref "U28") (pin "5") (pinfunction "D4/PWM_5") (pintype "unspecified"))
    )
    (net (code "6") (name "5") (class "Default")
      (node (ref "CN3-1") (pin "8") (pinfunction "8_8") (pintype "unspecified"))
      (node (ref "U28") (pin "6") (pinfunction "D5/PWM_6") (pintype "unspecified"))
    )
    (net (code "7") (name "6") (class "Default")
      (node (ref "CN3-1") (pin "10") (pinfunction "10_10") (pintype "unspecified"))
      (node (ref "U28") (pin "7") (pinfunction "D6/PWM_7") (pintype "unspecified"))
    )
    (net (code "8") (name "7") (class "Default")
      (node (ref "CN3-1") (pin "12") (pinfunction "12_12") (pintype "unspecified"))
      (node (ref "U28") (pin "8") (pinfunction "D7/PWM_8") (pintype "unspecified"))
    )
    (net (code "9") (name "8") (class "Default")
      (node (ref "CN3-1") (pin "14") (pinfunction "14_14") (pintype "unspecified"))
      (node (ref "U28") (pin "9") (pinfunction "D8/PWM_9") (pintype "unspecified"))
    )
    (net (code "10") (name "9") (class "Default")
      (node (ref "CN3-1") (pin "16") (pinfunction "16_16") (pintype "unspecified"))
      (node (ref "U28") (pin "10") (pinfunction "D9/PWM_10") (pintype "unspecified"))
    )
    (net (code "11") (name "10") (class "Default")
      (node (ref "CN3-1") (pin "18") (pinfunction "18_18") (pintype "unspecified"))
      (node (ref "U28") (pin "11") (pinfunction "D10/PWM_11") (pintype "unspecified"))
    )
    (net (code "12") (name "11") (class "Default")
      (node (ref "CN3-1") (pin "20") (pinfunction "20_20") (pintype "unspecified"))
      (node (ref "U28") (pin "12") (pinfunction "D11/PWM_12") (pintype "unspecified"))
    )
    (net (code "13") (name "12") (class "Default")
      (node (ref "CN3-1") (pin "3") (pinfunction "3_3") (pintype "unspecified"))
      (node (ref "U28") (pin "13") (pinfunction "D12/PWM_13") (pintype "unspecified"))
    )
    (net (code "14") (name "13") (class "Default")
      (node (ref "CN3-1") (pin "5") (pinfunction "5_5") (pintype "unspecified"))
      (node (ref "U28") (pin "14") (pinfunction "D13/PWM_14") (pintype "unspecified"))
    )
    (net (code "15") (name "14") (class "Default")
      (node (ref "CN3-1") (pin "7") (pinfunction "7_7") (pintype "unspecified"))
      (node (ref "U28") (pin "15") (pinfunction "D14/Tx3_15") (pintype "unspecified"))
    )
    (net (code "16") (name "15") (class "Default")
      (node (ref "CN3-1") (pin "9") (pinfunction "9_9") (pintype "unspecified"))
      (node (ref "U28") (pin "16") (pinfunction "D15/Rx3_16") (pintype "unspecified"))
    )
    (net (code "17") (name "16") (class "Default")
      (node (ref "CN3-1") (pin "11") (pinfunction "11_11") (pintype "unspecified"))
      (node (ref "U28") (pin "17") (pinfunction "D16/Tx2_17") (pintype "unspecified"))
    )
    (net (code "18") (name "17") (class "Default")
      (node (ref "CN3-1") (pin "13") (pinfunction "13_13") (pintype "unspecified"))
      (node (ref "U28") (pin "18") (pinfunction "D17/Rx2_18") (pintype "unspecified"))
    )
    (net (code "19") (name "18") (class "Default")
      (node (ref "CN3-1") (pin "15") (pinfunction "15_15") (pintype "unspecified"))
      (node (ref "U28") (pin "19") (pinfunction "D18/Tx1/INT3_19") (pintype "unspecified"))
    )
    (net (code "20") (name "19") (class "Default")
      (node (ref "CN3-1") (pin "17") (pinfunction "17_17") (pintype "unspecified"))
      (node (ref "U28") (pin "20") (pinfunction "D19/Rx1/INT2_20") (pintype "unspecified"))
    )
    (net (code "21") (name "20") (class "Default")
      (node (ref "CN3-1") (pin "19") (pinfunction "19_19") (pintype "unspecified"))
      (node (ref "U28") (pin "21") (pinfunction "D20/INT1/SDA_21") (pintype "unspecified"))
    )
    (net (code "22") (name "21") (class "Default")
      (node (ref "CN4-1") (pin "2") (pinfunction "2_2") (pintype "unspecified"))
      (node (ref "U28") (pin "22") (pinfunction "D21/INT0/SCL_22") (pintype "unspecified"))
    )
    (net (code "23") (name "22") (class "Default")
      (node (ref "CN4-1") (pin "4") (pinfunction "4_4") (pintype "unspecified"))
      (node (ref "U28") (pin "23") (pinfunction "D22_23") (pintype "unspecified"))
    )
    (net (code "24") (name "23") (class "Default")
      (node (ref "CN4-1") (pin "6") (pinfunction "6_6") (pintype "unspecified"))
      (node (ref "U28") (pin "24") (pinfunction "D23_24") (pintype "unspecified"))
    )
    (net (code "25") (name "24") (class "Default")
      (node (ref "CN4-1") (pin "8") (pinfunction "8_8") (pintype "unspecified"))
      (node (ref "U28") (pin "25") (pinfunction "D24_25") (pintype "unspecified"))
    )
    (net (code "26") (name "25") (class "Default")
      (node (ref "CN4-1") (pin "10") (pinfunction "10_10") (pintype "unspecified"))
      (node (ref "U28") (pin "26") (pinfunction "D25_26") (pintype "unspecified"))
    )
    (net (code "27") (name "26") (class "Default")
      (node (ref "CN4-1") (pin "12") (pinfunction "12_12") (pintype "unspecified"))
      (node (ref "U28") (pin "27") (pinfunction "D26_27") (pintype "unspecified"))
    )
    (net (code "28") (name "27") (class "Default")
      (node (ref "CN4-1") (pin "14") (pinfunction "14_14") (pintype "unspecified"))
      (node (ref "U28") (pin "28") (pinfunction "D27_28") (pintype "unspecified"))
    )
    (net (code "29") (name "28") (class "Default")
      (node (ref "CN4-1") (pin "16") (pinfunction "16_16") (pintype "unspecified"))
      (node (ref "U28") (pin "29") (pinfunction "D28_29") (pintype "unspecified"))
    )
    (net (code "30") (name "29") (class "Default")
      (node (ref "CN4-1") (pin "18") (pinfunction "18_18") (pintype "unspecified"))
      (node (ref "U28") (pin "30") (pinfunction "D29_30") (pintype "unspecified"))
    )
    (net (code "31") (name "30") (class "Default")
      (node (ref "CN4-1") (pin "20") (pinfunction "20_20") (pintype "unspecified"))
      (node (ref "U28") (pin "31") (pinfunction "D30_31") (pintype "unspecified"))
    )
    (net (code "32") (name "31") (class "Default")
      (node (ref "CN4-1") (pin "1") (pinfunction "1_1") (pintype "unspecified"))
      (node (ref "U28") (pin "32") (pinfunction "D31_32") (pintype "unspecified"))
    )
    (net (code "33") (name "32") (class "Default")
      (node (ref "CN4-1") (pin "3") (pinfunction "3_3") (pintype "unspecified"))
      (node (ref "U28") (pin "33") (pinfunction "D32_33") (pintype "unspecified"))
    )
    (net (code "34") (name "33") (class "Default")
      (node (ref "CN4-1") (pin "5") (pinfunction "5_5") (pintype "unspecified"))
      (node (ref "U28") (pin "34") (pinfunction "D33_34") (pintype "unspecified"))
    )
    (net (code "35") (name "34") (class "Default")
      (node (ref "CN4-1") (pin "7") (pinfunction "7_7") (pintype "unspecified"))
      (node (ref "U28") (pin "35") (pinfunction "D34_35") (pintype "unspecified"))
    )
    (net (code "36") (name "35") (class "Default")
      (node (ref "CN4-1") (pin "9") (pinfunction "9_9") (pintype "unspecified"))
      (node (ref "U28") (pin "36") (pinfunction "D35_36") (pintype "unspecified"))
    )
    (net (code "37") (name "36") (class "Default")
      (node (ref "CN4-1") (pin "11") (pinfunction "11_11") (pintype "unspecified"))
      (node (ref "U28") (pin "37") (pinfunction "D36_37") (pintype "unspecified"))
    )
    (net (code "38") (name "37") (class "Default")
      (node (ref "CN4-1") (pin "13") (pinfunction "13_13") (pintype "unspecified"))
      (node (ref "U28") (pin "38") (pinfunction "D37_38") (pintype "unspecified"))
    )
    (net (code "39") (name "38") (class "Default")
      (node (ref "CN4-1") (pin "15") (pinfunction "15_15") (pintype "unspecified"))
      (node (ref "U28") (pin "39") (pinfunction "D38_39") (pintype "unspecified"))
    )
    (net (code "40") (name "39") (class "Default")
      (node (ref "CN4-1") (pin "17") (pinfunction "17_17") (pintype "unspecified"))
      (node (ref "U28") (pin "40") (pinfunction "D39_40") (pintype "unspecified"))
    )
    (net (code "41") (name "40") (class "Default")
      (node (ref "CN4-1") (pin "19") (pinfunction "19_19") (pintype "unspecified"))
      (node (ref "U28") (pin "41") (pinfunction "D40_41") (pintype "unspecified"))
    )
    (net (code "42") (name "41") (class "Default")
      (node (ref "CN5-1") (pin "4") (pinfunction "4_4") (pintype "unspecified"))
      (node (ref "U28") (pin "42") (pinfunction "D41_42") (pintype "unspecified"))
    )
    (net (code "43") (name "42") (class "Default")
      (node (ref "CN5-1") (pin "6") (pinfunction "6_6") (pintype "unspecified"))
      (node (ref "U28") (pin "43") (pinfunction "D42_43") (pintype "unspecified"))
    )
    (net (code "44") (name "43") (class "Default")
      (node (ref "CN5-1") (pin "8") (pinfunction "8_8") (pintype "unspecified"))
      (node (ref "U28") (pin "44") (pinfunction "D43_44") (pintype "unspecified"))
    )
    (net (code "45") (name "44") (class "Default")
      (node (ref "CN5-1") (pin "10") (pinfunction "10_10") (pintype "unspecified"))
      (node (ref "U28") (pin "45") (pinfunction "PWM/D44_45") (pintype "unspecified"))
    )
    (net (code "46") (name "45") (class "Default")
      (node (ref "CN5-1") (pin "12") (pinfunction "12_12") (pintype "unspecified"))
      (node (ref "U28") (pin "46") (pinfunction "PWM/D45_46") (pintype "unspecified"))
    )
    (net (code "47") (name "46") (class "Default")
      (node (ref "CN5-1") (pin "14") (pinfunction "14_14") (pintype "unspecified"))
      (node (ref "U28") (pin "47") (pinfunction "PWM/D46_47") (pintype "unspecified"))
    )
    (net (code "48") (name "47") (class "Default")
      (node (ref "CN5-1") (pin "16") (pinfunction "16_16") (pintype "unspecified"))
      (node (ref "U28") (pin "48") (pinfunction "D47_48") (pintype "unspecified"))
    )
    (net (code "49") (name "48") (class "Default")
      (node (ref "CN5-1") (pin "18") (pinfunction "18_18") (pintype "unspecified"))
      (node (ref "U28") (pin "49") (pinfunction "D48_49") (pintype "unspecified"))
    )
    (net (code "50") (name "49") (class "Default")
      (node (ref "CN5-1") (pin "20") (pinfunction "20_20") (pintype "unspecified"))
      (node (ref "U28") (pin "50") (pinfunction "D49_50") (pintype "unspecified"))
    )
    (net (code "51") (name "A0") (class "Default")
      (node (ref "CN5-1") (pin "3") (pinfunction "3_3") (pintype "unspecified"))
      (node (ref "CN5-2") (pin "3") (pinfunction "3_3") (pintype "unspecified"))
      (node (ref "U28") (pin "55") (pinfunction "A0_55") (pintype "unspecified"))
    )
    (net (code "52") (name "A1") (class "Default")
      (node (ref "CN5-1") (pin "5") (pinfunction "5_5") (pintype "unspecified"))
      (node (ref "CN5-2") (pin "5") (pinfunction "5_5") (pintype "unspecified"))
      (node (ref "U28") (pin "56") (pinfunction "A1_56") (pintype "unspecified"))
    )
    (net (code "53") (name "A2") (class "Default")
      (node (ref "CN5-1") (pin "7") (pinfunction "7_7") (pintype "unspecified"))
      (node (ref "CN5-2") (pin "7") (pinfunction "7_7") (pintype "unspecified"))
      (node (ref "U28") (pin "57") (pinfunction "A2_57") (pintype "unspecified"))
    )
    (net (code "54") (name "A3") (class "Default")
      (node (ref "CN5-1") (pin "9") (pinfunction "9_9") (pintype "unspecified"))
      (node (ref "CN5-2") (pin "9") (pinfunction "9_9") (pintype "unspecified"))
      (node (ref "U28") (pin "58") (pinfunction "A3_58") (pintype "unspecified"))
    )
    (net (code "55") (name "A4") (class "Default")
      (node (ref "CN5-1") (pin "11") (pinfunction "11_11") (pintype "unspecified"))
      (node (ref "CN5-2") (pin "11") (pinfunction "11_11") (pintype "unspecified"))
      (node (ref "U28") (pin "59") (pinfunction "A4_59") (pintype "unspecified"))
    )
    (net (code "56") (name "A5") (class "Default")
      (node (ref "U28") (pin "60") (pinfunction "A5_60") (pintype "unspecified"))
    )
    (net (code "57") (name "A6") (class "Default")
      (node (ref "U28") (pin "61") (pinfunction "A6_61") (pintype "unspecified"))
    )
    (net (code "58") (name "A7") (class "Default")
      (node (ref "U28") (pin "62") (pinfunction "A7_62") (pintype "unspecified"))
    )
    (net (code "59") (name "A8") (class "Default")
      (node (ref "U28") (pin "63") (pinfunction "A8_63") (pintype "unspecified"))
    )
    (net (code "60") (name "EN#") (class "Default")
      (node (ref "SW9") (pin "2") (pinfunction "2_2") (pintype "unspecified"))
      (node (ref "U2-MASTER") (pin "21") (pinfunction "EN#_21") (pintype "unspecified"))
      (node (ref "U3-SLAVE") (pin "21") (pinfunction "EN#_21") (pintype "unspecified"))
    )
    (net (code "61") (name "GPIO3") (class "Default")
      (node (ref "CN3-2") (pin "4") (pinfunction "4_4") (pintype "unspecified"))
    )
    (net (code "62") (name "GPIO4") (class "Default")
      (node (ref "CN3-2") (pin "6") (pinfunction "6_6") (pintype "unspecified"))
    )
    (net (code "63") (name "GPIO5") (class "Default")
      (node (ref "CN3-2") (pin "8") (pinfunction "8_8") (pintype "unspecified"))
      (node (ref "R7") (pin "1") (pinfunction "1_1") (pintype "unspecified"))
      (node (ref "SW9") (pin "3") (pinfunction "3_3") (pintype "unspecified"))
    )
    (net (code "64") (name "GPIO6") (class "Default")
      (node (ref "CN1") (pin "1") (pinfunction "1_1") (pintype "unspecified"))
      (node (ref "CN3-2") (pin "10") (pinfunction "10_10") (pintype "unspecified"))
    )
    (net (code "65") (name "GPIO7") (class "Default")
      (node (ref "CN1") (pin "2") (pinfunction "2_2") (pintype "unspecified"))
      (node (ref "CN3-2") (pin "12") (pinfunction "12_12") (pintype "unspecified"))
    )
    (net (code "66") (name "GPIO8") (class "Default")
      (node (ref "C2") (pin "1") (pinfunction "1_1") (pintype "unspecified"))
      (node (ref "CN3-2") (pin "14") (pinfunction "14_14") (pintype "unspecified"))
      (node (ref "FMS") (pin "7") (pinfunction "SW_7") (pintype "unspecified"))
      (node (ref "RN1") (pin "5") (pinfunction "5_5") (pintype "input"))
    )
    (net (code "67") (name "GPIO9") (class "Default")
      (node (ref "CN3-2") (pin "16") (pinfunction "16_16") (pintype "unspecified"))
    )
    (net (code "68") (name "GPIO10") (class "Default")
      (node (ref "CN3-2") (pin "18") (pinfunction "18_18") (pintype "unspecified"))
    )
    (net (code "69") (name "GPIO11") (class "Default")
      (node (ref "C1") (pin "1") (pinfunction "1_1") (pintype "unspecified"))
      (node (ref "CN3-2") (pin "20") (pinfunction "20_20") (pintype "unspecified"))
      (node (ref "CRS/BARO") (pin "7") (pinfunction "SW_7") (pintype "unspecified"))
      (node (ref "RN3") (pin "5") (pinfunction "5_5") (pintype "input"))
    )
    (net (code "70") (name "GPIO12") (class "Default")
      (node (ref "CN3-2") (pin "3") (pinfunction "3_3") (pintype "unspecified"))
    )
    (net (code "71") (name "GPIO13") (class "Default")
      (node (ref "CN3-2") (pin "5") (pinfunction "5_5") (pintype "unspecified"))
    )
    (net (code "72") (name "GPIO14") (class "Default")
      (node (ref "CN3-2") (pin "7") (pinfunction "7_7") (pintype "unspecified"))
    )
    (net (code "73") (name "GPIO15") (class "Default")
      (node (ref "C11") (pin "2") (pinfunction "2_2") (pintype "unspecified"))
      (node (ref "CN3-2") (pin "9") (pinfunction "9_9") (pintype "unspecified"))
      (node (ref "RANGE_PAN1") (pin "6") (pinfunction "COM_6") (pintype "unspecified"))
      (node (ref "RN6") (pin "1") (pinfunction "1_1") (pintype "input"))
    )
    (net (code "74") (name "GPIO16") (class "Default")
      (node (ref "CN3-2") (pin "11") (pinfunction "11_11") (pintype "unspecified"))
      (node (ref "FMS") (pin "1") (pinfunction "A1_1") (pintype "unspecified"))
      (node (ref "RN1") (pin "8") (pinfunction "8_8") (pintype "input"))
    )
    (net (code "75") (name "GPIO17") (class "Default")
      (node (ref "CN3-2") (pin "13") (pinfunction "13_13") (pintype "unspecified"))
      (node (ref "FMS") (pin "3") (pinfunction "B1_3") (pintype "unspecified"))
      (node (ref "RN1") (pin "6") (pinfunction "6_6") (pintype "input"))
    )
    (net (code "76") (name "GPIO18") (class "Default")
      (node (ref "C10") (pin "1") (pinfunction "1_1") (pintype "unspecified"))
      (node (ref "CN3-2") (pin "15") (pinfunction "15_15") (pintype "unspecified"))
      (node (ref "RANGE_PAN1") (pin "7") (pinfunction "E_B_7") (pintype "unspecified"))
      (node (ref "RN6") (pin "4") (pinfunction "4_4") (pintype "input"))
    )
    (net (code "77") (name "GPIO19") (class "Default")
      (node (ref "C8") (pin "1") (pinfunction "1_1") (pintype "unspecified"))
      (node (ref "CN3-2") (pin "17") (pinfunction "17_17") (pintype "unspecified"))
      (node (ref "RANGE_PAN1") (pin "8") (pinfunction "E_A_8") (pintype "unspecified"))
      (node (ref "RN6") (pin "3") (pinfunction "3_3") (pintype "input"))
    )
    (net (code "78") (name "GPIO20") (class "Default")
      (node (ref "CN3-2") (pin "19") (pinfunction "19_19") (pintype "unspecified"))
      (node (ref "FMS") (pin "4") (pinfunction "B2_4") (pintype "unspecified"))
      (node (ref "RN2") (pin "8") (pinfunction "8_8") (pintype "input"))
    )
    (net (code "79") (name "GPIO21") (class "Default")
      (node (ref "CN4-2") (pin "2") (pinfunction "2_2") (pintype "unspecified"))
      (node (ref "FMS") (pin "6") (pinfunction "A2_6") (pintype "unspecified"))
      (node (ref "RN2") (pin "5") (pinfunction "5_5") (pintype "input"))
    )
    (net (code "80") (name "GPIO22") (class "Default")
      (node (ref "CN4-2") (pin "4") (pinfunction "4_4") (pintype "unspecified"))
      (node (ref "CRS/BARO") (pin "4") (pinfunction "B2_4") (pintype "unspecified"))
      (node (ref "RN4") (pin "1") (pinfunction "1_1") (pintype "input"))
    )
    (net (code "81") (name "GPIO23") (class "Default")
      (node (ref "CN4-2") (pin "6") (pinfunction "6_6") (pintype "unspecified"))
      (node (ref "CRS/BARO") (pin "6") (pinfunction "A2_6") (pintype "unspecified"))
      (node (ref "RN4") (pin "4") (pinfunction "4_4") (pintype "input"))
    )
    (net (code "82") (name "GPIO24") (class "Default")
      (node (ref "CN4-2") (pin "8") (pinfunction "8_8") (pintype "unspecified"))
      (node (ref "CRS/BARO") (pin "1") (pinfunction "A1_1") (pintype "unspecified"))
      (node (ref "RN3") (pin "8") (pinfunction "8_8") (pintype "input"))
    )
    (net (code "83") (name "GPIO25") (class "Default")
      (node (ref "CN4-2") (pin "10") (pinfunction "10_10") (pintype "unspecified"))
      (node (ref "CRS/BARO") (pin "3") (pinfunction "B1_3") (pintype "unspecified"))
      (node (ref "RN3") (pin "6") (pinfunction "6_6") (pintype "input"))
    )
    (net (code "84") (name "GPIO26") (class "Default")
      (node (ref "CN4-2") (pin "12") (pinfunction "12_12") (pintype "unspecified"))
      (node (ref "RANGE_PAN1") (pin "A") (pinfunction "A_A") (pintype "unspecified"))
      (node (ref "RN5") (pin "5") (pinfunction "5_5") (pintype "input"))
    )
    (net (code "85") (name "GPIO27") (class "Default")
      (node (ref "CN4-2") (pin "14") (pinfunction "14_14") (pintype "unspecified"))
      (node (ref "RANGE_PAN1") (pin "B") (pinfunction "B_B") (pintype "unspecified"))
      (node (ref "RN5") (pin "6") (pinfunction "6_6") (pintype "input"))
    )
    (net (code "86") (name "GPIO28") (class "Default")
      (node (ref "CN4-2") (pin "16") (pinfunction "16_16") (pintype "unspecified"))
      (node (ref "RANGE_PAN1") (pin "C") (pinfunction "C_C") (pintype "unspecified"))
      (node (ref "RN5") (pin "7") (pinfunction "7_7") (pintype "input"))
    )
    (net (code "87") (name "GPIO29") (class "Default")
      (node (ref "CN4-2") (pin "18") (pinfunction "18_18") (pintype "unspecified"))
      (node (ref "RANGE_PAN1") (pin "D") (pinfunction "D_D") (pintype "unspecified"))
      (node (ref "RN5") (pin "8") (pinfunction "8_8") (pintype "input"))
    )
    (net (code "88") (name "GPIO30") (class "Default")
      (node (ref "C7") (pin "1") (pinfunction "1_1") (pintype "unspecified"))
      (node (ref "CN4-2") (pin "20") (pinfunction "20_20") (pintype "unspecified"))
      (node (ref "RN8") (pin "8") (pinfunction "8_8") (pintype "input"))
      (node (ref "SW6") (pin "1") (pinfunction "1_1") (pintype "unspecified"))
    )
    (net (code "89") (name "GPIO31") (class "Default")
      (node (ref "C4") (pin "1") (pinfunction "1_1") (pintype "unspecified"))
      (node (ref "CN4-2") (pin "1") (pinfunction "1_1") (pintype "unspecified"))
      (node (ref "RN8") (pin "6") (pinfunction "6_6") (pintype "input"))
      (node (ref "SW5") (pin "1") (pinfunction "1_1") (pintype "unspecified"))
    )
    (net (code "90") (name "GPIO32") (class "Default")
      (node (ref "C3") (pin "1") (pinfunction "1_1") (pintype "unspecified"))
      (node (ref "CN4-2") (pin "3") (pinfunction "3_3") (pintype "unspecified"))
      (node (ref "RN8") (pin "5") (pinfunction "5_5") (pintype "input"))
      (node (ref "SW3") (pin "1") (pinfunction "1_1") (pintype "unspecified"))
    )
    (net (code "91") (name "GPIO33") (class "Default")
      (node (ref "C9") (pin "1") (pinfunction "1_1") (pintype "unspecified"))
      (node (ref "CN4-2") (pin "5") (pinfunction "5_5") (pintype "unspecified"))
      (node (ref "RN7") (pin "5") (pinfunction "5_5") (pintype "input"))
      (node (ref "SW1") (pin "1") (pinfunction "1_1") (pintype "unspecified"))
    )
    (net (code "92") (name "GPIO34") (class "Default")
      (node (ref "C5") (pin "1") (pinfunction "1_1") (pintype "unspecified"))
      (node (ref "CN4-2") (pin "7") (pinfunction "7_7") (pintype "unspecified"))
      (node (ref "RN7") (pin "6") (pinfunction "6_6") (pintype "input"))
      (node (ref "SW2") (pin "1") (pinfunction "1_1") (pintype "unspecified"))
    )
    (net (code "93") (name "GPIO35") (class "Default")
      (node (ref "C6") (pin "1") (pinfunction "1_1") (pintype "unspecified"))
      (node (ref "CN4-2") (pin "9") (pinfunction "9_9") (pintype "unspecified"))
      (node (ref "RN7") (pin "8") (pinfunction "8_8") (pintype "input"))
      (node (ref "SW4") (pin "1") (pinfunction "1_1") (pintype "unspecified"))
    )
    (net (code "94") (name "GPIO36") (class "Default")
      (node (ref "CN4-2") (pin "11") (pinfunction "11_11") (pintype "unspecified"))
      (node (ref "R2") (pin "2") (pinfunction "2_2") (pintype "unspecified"))
      (node (ref "SW8") (pin "1") (pinfunction "C_1") (pintype "unspecified"))
    )
    (net (code "95") (name "GPIO37") (class "Default")
      (node (ref "CN4-2") (pin "13") (pinfunction "13_13") (pintype "unspecified"))
      (node (ref "SW8") (pin "5") (pinfunction "L+_5") (pintype "unspecified"))
    )
    (net (code "96") (name "GPIO38") (class "Default")
      (node (ref "CN4-2") (pin "15") (pinfunction "15_15") (pintype "unspecified"))
      (node (ref "R3") (pin "2") (pinfunction "2_2") (pintype "unspecified"))
      (node (ref "SW7") (pin "1") (pinfunction "C_1") (pintype "unspecified"))
    )
    (net (code "97") (name "GPIO39") (class "Default")
      (node (ref "CN4-2") (pin "17") (pinfunction "17_17") (pintype "unspecified"))
      (node (ref "SW7") (pin "5") (pinfunction "L+_5") (pintype "unspecified"))
    )
    (net (code "98") (name "GPIO40") (class "Default")
      (node (ref "CN4-2") (pin "19") (pinfunction "19_19") (pintype "unspecified"))
    )
    (net (code "99") (name "GPIO41") (class "Default")
      (node (ref "CN5-2") (pin "4") (pinfunction "4_4") (pintype "unspecified"))
    )
    (net (code "100") (name "GPIO42") (class "Default")
      (node (ref "CN5-2") (pin "6") (pinfunction "6_6") (pintype "unspecified"))
    )
    (net (code "101") (name "GPIO43") (class "Default")
      (node (ref "CN5-2") (pin "8") (pinfunction "8_8") (pintype "unspecified"))
      (node (ref "R30") (pin "2") (pinfunction "2_2") (pintype "unspecified"))
      (node (ref "U1") (pin "4") (pinfunction "RST_4") (pintype "unspecified"))
    )
    (net (code "102") (name "GPIO44") (class "Default")
      (node (ref "CN5-2") (pin "10") (pinfunction "10_10") (pintype "unspecified"))
    )
    (net (code "103") (name "GPIO45") (class "Default")
      (node (ref "CN5-2") (pin "12") (pinfunction "12_12") (pintype "unspecified"))
    )
    (net (code "104") (name "GPIO46") (class "Default")
      (node (ref "CN5-2") (pin "14") (pinfunction "14_14") (pintype "unspecified"))
    )
    (net (code "105") (name "GPIO47") (class "Default")
      (node (ref "CN5-2") (pin "16") (pinfunction "16_16") (pintype "unspecified"))
    )
    (net (code "106") (name "GPIO48") (class "Default")
      (node (ref "CN5-2") (pin "18") (pinfunction "18_18") (pintype "unspecified"))
    )
    (net (code "107") (name "GPIO49") (class "Default")
      (node (ref "CN5-2") (pin "20") (pinfunction "20_20") (pintype "unspecified"))
      (node (ref "U2-MASTER") (pin "4") (pinfunction "LAT_4") (pintype "unspecified"))
      (node (ref "U3-SLAVE") (pin "4") (pinfunction "LAT_4") (pintype "unspecified"))
    )
    (net (code "108") (name "LAT") (class "Default")
      (node (ref "U28") (pin "54") (pinfunction "SS/D53_54") (pintype "unspecified"))
    )
    (net (code "109") (name "MISO") (class "Default")
      (node (ref "CN5-1") (pin "13") (pinfunction "13_13") (pintype "unspecified"))
      (node (ref "CN5-2") (pin "13") (pinfunction "13_13") (pintype "unspecified"))
      (node (ref "U28") (pin "51") (pinfunction "MISO/D50_51") (pintype "unspecified"))
    )
    (net (code "110") (name "MOSI") (class "Default")
      (node (ref "CN5-1") (pin "15") (pinfunction "15_15") (pintype "unspecified"))
      (node (ref "CN5-2") (pin "15") (pinfunction "15_15") (pintype "unspecified"))
      (node (ref "U2-MASTER") (pin "2") (pinfunction "DAI_2") (pintype "unspecified"))
      (node (ref "U28") (pin "52") (pinfunction "MOSI/D51_52") (pintype "unspecified"))
    )
    (net (code "112") (name "Net-(ALIM_EXTERNE_7.5V-Pad1)") (class "Default")
      (node (ref "ALIM_EXTERNE_7.5V") (pin "1") (pinfunction "1_1") (pintype "unspecified"))
      (node (ref "U28") (pin "71") (pinfunction "VIN_71") (pintype "unspecified"))
    )
    (net (code "113") (name "Net-(ALIM_EXTERNE_7.5V-Pad2)") (class "Default")
      (node (ref "ALIM_EXTERNE_7.5V") (pin "2") (pinfunction "2_2") (pintype "unspecified"))
      (node (ref "U28") (pin "73") (pinfunction "GND_73") (pintype "unspecified"))
    )
    (net (code "114") (name "Net-(BUZ1--)") (class "Default")
      (node (ref "BUZ1") (pin "2") (pinfunction "-_2") (pintype "unspecified"))
      (node (ref "D1") (pin "2") (pinfunction "A_2") (pintype "unspecified"))
      (node (ref "R1") (pin "3") (pinfunction "3_3") (pintype "unspecified"))
    )
    (net (code "115") (name "Net-(CN2-Pad1)") (class "Default")
      (node (ref "CN2") (pin "1") (pinfunction "1_1") (pintype "unspecified"))
      (node (ref "C_LED2") (pin "1") (pinfunction "1_1") (pintype "unspecified"))
      (node (ref "R8") (pin "2") (pinfunction "2_2") (pintype "unspecified"))
    )
    (net (code "116") (name "Net-(CN3-Pad1)") (class "Default")
      (node (ref "CN3") (pin "1") (pinfunction "1_1") (pintype "unspecified"))
      (node (ref "C_LED1") (pin "1") (pinfunction "1_1") (pintype "unspecified"))
      (node (ref "R9") (pin "2") (pinfunction "2_2") (pintype "unspecified"))
    )
    (net (code "117") (name "Net-(CN4-Pad1)") (class "Default")
      (node (ref "CN4") (pin "1") (pinfunction "1_1") (pintype "unspecified"))
      (node (ref "R8") (pin "1") (pinfunction "1_1") (pintype "unspecified"))
    )
    (net (code "118") (name "Net-(CN4-Pad2)") (class "Default")
      (node (ref "CN4") (pin "2") (pinfunction "2_2") (pintype "unspecified"))
      (node (ref "R9") (pin "1") (pinfunction "1_1") (pintype "unspecified"))
    )
    (net (code "119") (name "Net-(LED1-K)") (class "Default")
      (node (ref "LED1") (pin "1") (pinfunction "K_1") (pintype "unspecified"))
      (node (ref "U2-MASTER") (pin "5") (pinfunction "OUT0_5") (pintype "unspecified"))
    )
    (net (code "120") (name "Net-(LED2-K)") (class "Default")
      (node (ref "LED2") (pin "1") (pinfunction "K_1") (pintype "unspecified"))
      (node (ref "U2-MASTER") (pin "6") (pinfunction "OUT1_6") (pintype "unspecified"))
    )
    (net (code "121") (name "Net-(LED3-K)") (class "Default")
      (node (ref "LED3") (pin "1") (pinfunction "K_1") (pintype "unspecified"))
      (node (ref "U2-MASTER") (pin "7") (pinfunction "OUT2_7") (pintype "unspecified"))
    )
    (net (code "122") (name "Net-(LED4-K)") (class "Default")
      (node (ref "LED4") (pin "1") (pinfunction "K_1") (pintype "unspecified"))
      (node (ref "U2-MASTER") (pin "8") (pinfunction "OUT3_8") (pintype "unspecified"))
    )
    (net (code "123") (name "Net-(LED5-K)") (class "Default")
      (node (ref "LED5") (pin "1") (pinfunction "K_1") (pintype "unspecified"))
      (node (ref "U2-MASTER") (pin "9") (pinfunction "OUT4_9") (pintype "unspecified"))
    )
    (net (code "124") (name "Net-(LED6-K)") (class "Default")
      (node (ref "LED6") (pin "1") (pinfunction "K_1") (pintype "unspecified"))
      (node (ref "U2-MASTER") (pin "10") (pinfunction "OUT5_10") (pintype "unspecified"))
    )
    (net (code "125") (name "Net-(LED7-K)") (class "Default")
      (node (ref "LED7") (pin "1") (pinfunction "K_1") (pintype "unspecified"))
      (node (ref "U2-MASTER") (pin "11") (pinfunction "OUT6_11") (pintype "unspecified"))
    )
    (net (code "126") (name "Net-(LED8-K)") (class "Default")
      (node (ref "LED8") (pin "1") (pinfunction "K_1") (pintype "unspecified"))
      (node (ref "U2-MASTER") (pin "12") (pinfunction "OUT7_12") (pintype "unspecified"))
    )
    (net (code "127") (name "Net-(LED9-K)") (class "Default")
      (node (ref "LED9") (pin "1") (pinfunction "K_1") (pintype "unspecified"))
      (node (ref "U2-MASTER") (pin "15") (pinfunction "OUT10_15") (pintype "unspecified"))
    )
    (net (code "128") (name "Net-(LED10-K)") (class "Default")
      (node (ref "LED10") (pin "1") (pinfunction "K_1") (pintype "unspecified"))
      (node (ref "U2-MASTER") (pin "14") (pinfunction "OUT9_14") (pintype "unspecified"))
    )
    (net (code "129") (name "Net-(LED11-K)") (class "Default")
      (node (ref "LED11") (pin "1") (pinfunction "K_1") (pintype "unspecified"))
      (node (ref "U2-MASTER") (pin "13") (pinfunction "OUT8_13") (pintype "unspecified"))
    )
    (net (code "130") (name "Net-(LED12-K)") (class "Default")
      (node (ref "LED12") (pin "1") (pinfunction "K_1") (pintype "unspecified"))
      (node (ref "U3-SLAVE") (pin "5") (pinfunction "OUT0_5") (pintype "unspecified"))
    )
    (net (code "131") (name "Net-(LED13-K)") (class "Default")
      (node (ref "LED13") (pin "1") (pinfunction "K_1") (pintype "unspecified"))
      (node (ref "U3-SLAVE") (pin "6") (pinfunction "OUT1_6") (pintype "unspecified"))
    )
    (net (code "132") (name "Net-(LED14-K)") (class "Default")
      (node (ref "LED14") (pin "1") (pinfunction "K_1") (pintype "unspecified"))
      (node (ref "U3-SLAVE") (pin "7") (pinfunction "OUT2_7") (pintype "unspecified"))
    )
    (net (code "133") (name "Net-(LED15-K)") (class "Default")
      (node (ref "LED15") (pin "1") (pinfunction "K_1") (pintype "unspecified"))
      (node (ref "U3-SLAVE") (pin "8") (pinfunction "OUT3_8") (pintype "unspecified"))
    )
    (net (code "134") (name "Net-(LED16-K)") (class "Default")
      (node (ref "LED16") (pin "1") (pinfunction "K_1") (pintype "unspecified"))
      (node (ref "U3-SLAVE") (pin "9") (pinfunction "OUT4_9") (pintype "unspecified"))
    )
    (net (code "135") (name "Net-(LED17-K)") (class "Default")
      (node (ref "LED17") (pin "1") (pinfunction "K_1") (pintype "unspecified"))
      (node (ref "U3-SLAVE") (pin "10") (pinfunction "OUT5_10") (pintype "unspecified"))
    )
    (net (code "136") (name "Net-(LED18-K)") (class "Default")
      (node (ref "LED18") (pin "1") (pinfunction "K_1") (pintype "unspecified"))
      (node (ref "U3-SLAVE") (pin "12") (pinfunction "OUT7_12") (pintype "unspecified"))
    )
    (net (code "137") (name "Net-(LED19-K)") (class "Default")
      (node (ref "LED19") (pin "1") (pinfunction "K_1") (pintype "unspecified"))
      (node (ref "U3-SLAVE") (pin "14") (pinfunction "OUT9_14") (pintype "unspecified"))
    )
    (net (code "138") (name "Net-(LED20-K)") (class "Default")
      (node (ref "LED20") (pin "1") (pinfunction "K_1") (pintype "unspecified"))
      (node (ref "U3-SLAVE") (pin "13") (pinfunction "OUT8_13") (pintype "unspecified"))
    )
    (net (code "139") (name "Net-(LED21-K)") (class "Default")
      (node (ref "LED21") (pin "1") (pinfunction "K_1") (pintype "unspecified"))
      (node (ref "U2-MASTER") (pin "17") (pinfunction "OUT12_17") (pintype "unspecified"))
    )
    (net (code "140") (name "Net-(Q1-B)") (class "Default")
      (node (ref "Q1") (pin "1") (pinfunction "B_1") (pintype "input"))
      (node (ref "R36") (pin "1") (pinfunction "1_1") (pintype "unspecified"))
    )
    (net (code "141") (name "Net-(Q1-C)") (class "Default")
      (node (ref "Q1") (pin "3") (pinfunction "C_3") (pintype "input"))
      (node (ref "R1") (pin "2") (pinfunction "2_2") (pintype "unspecified"))
    )
    (net (code "142") (name "Net-(SW7-G-)") (class "Default")
      (node (ref "R10") (pin "1") (pinfunction "1_1") (pintype "unspecified"))
      (node (ref "SW7") (pin "7") (pinfunction "G-_7") (pintype "unspecified"))
    )
    (net (code "143") (name "Net-(SW7-R-)") (class "Default")
      (node (ref "R5") (pin "1") (pinfunction "1_1") (pintype "unspecified"))
      (node (ref "SW7") (pin "4") (pinfunction "R-_4") (pintype "unspecified"))
    )
    (net (code "144") (name "Net-(SW8-R-)") (class "Default")
      (node (ref "R4") (pin "1") (pinfunction "1_1") (pintype "unspecified"))
      (node (ref "SW8") (pin "4") (pinfunction "R-_4") (pintype "unspecified"))
    )
    (net (code "145") (name "Net-(U1-CONT)") (class "Default")
      (node (ref "C13") (pin "1") (pinfunction "1_1") (pintype "unspecified"))
      (node (ref "U1") (pin "5") (pinfunction "CONT_5") (pintype "unspecified"))
    )
    (net (code "146") (name "Net-(U1-DISCH)") (class "Default")
      (node (ref "RA-U35") (pin "2") (pinfunction "2_2") (pintype "unspecified"))
      (node (ref "RB-U37") (pin "1") (pinfunction "1_1") (pintype "unspecified"))
      (node (ref "U1") (pin "7") (pinfunction "DISCH_7") (pintype "unspecified"))
    )
    (net (code "147") (name "Net-(U1-OUT)") (class "Default")
      (node (ref "R36") (pin "2") (pinfunction "2_2") (pintype "unspecified"))
      (node (ref "U1") (pin "3") (pinfunction "OUT_3") (pintype "unspecified"))
    )
    (net (code "148") (name "Net-(U1-THRES)") (class "Default")
      (node (ref "C_TIMING-C12") (pin "1") (pinfunction "1_1") (pintype "unspecified"))
      (node (ref "RB-U37") (pin "2") (pinfunction "2_2") (pintype "unspecified"))
      (node (ref "U1") (pin "2") (pinfunction "TRIG_2") (pintype "unspecified"))
      (node (ref "U1") (pin "6") (pinfunction "THRES_6") (pintype "unspecified"))
    )
    (net (code "149") (name "Net-(U2-MASTER-REXT)") (class "Default")
      (node (ref "R11") (pin "2") (pinfunction "2_2") (pintype "unspecified"))
      (node (ref "U2-MASTER") (pin "23") (pinfunction "REXT_23") (pintype "unspecified"))
    )
    (net (code "150") (name "Net-(U3-SLAVE-REXT)") (class "Default")
      (node (ref "R6") (pin "2") (pinfunction "2_2") (pintype "unspecified"))
      (node (ref "U3-SLAVE") (pin "23") (pinfunction "REXT_23") (pintype "unspecified"))
    )
    (net (code "151") (name "REXT") (class "Default")
      (node (ref "C1") (pin "2") (pinfunction "2_2") (pintype "unspecified"))
      (node (ref "C10") (pin "2") (pinfunction "2_2") (pintype "unspecified"))
      (node (ref "C11") (pin "1") (pinfunction "1_1") (pintype "unspecified"))
      (node (ref "C12") (pin "2") (pinfunction "2_2") (pintype "unspecified"))
      (node (ref "C13") (pin "2") (pinfunction "2_2") (pintype "unspecified"))
      (node (ref "C14") (pin "2") (pinfunction "2_2") (pintype "unspecified"))
      (node (ref "C15") (pin "2") (pinfunction "2_2") (pintype "input"))
      (node (ref "C16") (pin "2") (pinfunction "2_2") (pintype "input"))
      (node (ref "C2") (pin "2") (pinfunction "2_2") (pintype "unspecified"))
      (node (ref "C3") (pin "2") (pinfunction "2_2") (pintype "unspecified"))
      (node (ref "C4") (pin "2") (pinfunction "2_2") (pintype "unspecified"))
      (node (ref "C5") (pin "2") (pinfunction "2_2") (pintype "unspecified"))
      (node (ref "C6") (pin "2") (pinfunction "2_2") (pintype "unspecified"))
      (node (ref "C7") (pin "2") (pinfunction "2_2") (pintype "unspecified"))
      (node (ref "C8") (pin "2") (pinfunction "2_2") (pintype "unspecified"))
      (node (ref "C9") (pin "2") (pinfunction "2_2") (pintype "unspecified"))
      (node (ref "CN1") (pin "3") (pinfunction "3_3") (pintype "unspecified"))
      (node (ref "CN2") (pin "3") (pinfunction "3_3") (pintype "unspecified"))
      (node (ref "CN3") (pin "3") (pinfunction "3_3") (pintype "unspecified"))
      (node (ref "CN3-1") (pin "2") (pinfunction "2_2") (pintype "unspecified"))
      (node (ref "CN3-2") (pin "2") (pinfunction "2_2") (pintype "unspecified"))
      (node (ref "CN4") (pin "4") (pinfunction "4_4") (pintype "unspecified"))
      (node (ref "CN5-1") (pin "1") (pinfunction "1_1") (pintype "unspecified"))
      (node (ref "CN5-2") (pin "1") (pinfunction "1_1") (pintype "unspecified"))
      (node (ref "CRS/BARO") (pin "2") (pinfunction "GND1_2") (pintype "unspecified"))
      (node (ref "CRS/BARO") (pin "5") (pinfunction "GND2_5") (pintype "unspecified"))
      (node (ref "CRS/BARO") (pin "8") (pinfunction "GND_8") (pintype "unspecified"))
      (node (ref "CRS/BARO") (pin "9") (pinfunction "GND_9") (pintype "unspecified"))
      (node (ref "C_LED1") (pin "2") (pinfunction "2_2") (pintype "unspecified"))
      (node (ref "C_LED2") (pin "2") (pinfunction "2_2") (pintype "unspecified"))
      (node (ref "C_TIMING-C12") (pin "2") (pinfunction "2_2") (pintype "unspecified"))
      (node (ref "FMS") (pin "2") (pinfunction "GND1_2") (pintype "unspecified"))
      (node (ref "FMS") (pin "5") (pinfunction "GND2_5") (pintype "unspecified"))
      (node (ref "FMS") (pin "8") (pinfunction "GND_8") (pintype "unspecified"))
      (node (ref "FMS") (pin "9") (pinfunction "GND_9") (pintype "unspecified"))
      (node (ref "Q1") (pin "2") (pinfunction "E_2") (pintype "input"))
      (node (ref "R10") (pin "2") (pinfunction "2_2") (pintype "unspecified"))
      (node (ref "R11") (pin "1") (pinfunction "1_1") (pintype "unspecified"))
      (node (ref "R4") (pin "2") (pinfunction "2_2") (pintype "unspecified"))
      (node (ref "R5") (pin "2") (pinfunction "2_2") (pintype "unspecified"))
      (node (ref "R6") (pin "1") (pinfunction "1_1") (pintype "unspecified"))
      (node (ref "R7") (pin "2") (pinfunction "2_2") (pintype "unspecified"))
      (node (ref "RANGE_PAN1") (pin "10") (pinfunction "10_10") (pintype "unspecified"))
      (node (ref "RANGE_PAN1") (pin "5") (pinfunction "PUSH_5") (pintype "unspecified"))
      (node (ref "RANGE_PAN1") (pin "9") (pinfunction "E_C_9") (pintype "unspecified"))
      (node (ref "SW1") (pin "3") (pinfunction "3_3") (pintype "unspecified"))
      (node (ref "SW2") (pin "3") (pinfunction "3_3") (pintype "unspecified"))
      (node (ref "SW3") (pin "3") (pinfunction "3_3") (pintype "unspecified"))
      (node (ref "SW4") (pin "3") (pinfunction "3_3") (pintype "unspecified"))
      (node (ref "SW5") (pin "3") (pinfunction "3_3") (pintype "unspecified"))
      (node (ref "SW6") (pin "3") (pinfunction "3_3") (pintype "unspecified"))
      (node (ref "SW7") (pin "2") (pinfunction "NO_2") (pintype "unspecified"))
      (node (ref "SW8") (pin "2") (pinfunction "NO_2") (pintype "unspecified"))
      (node (ref "SW9") (pin "1") (pinfunction "1_1") (pintype "unspecified"))
      (node (ref "U1") (pin "1") (pinfunction "GND_1") (pintype "unspecified"))
      (node (ref "U2-MASTER") (pin "1") (pinfunction "GND_1") (pintype "unspecified"))
      (node (ref "U28") (pin "74") (pinfunction "GND_74") (pintype "unspecified"))
      (node (ref "U3-SLAVE") (pin "1") (pinfunction "GND_1") (pintype "unspecified"))
    )
    (net (code "152") (name "SCK") (class "Default")
      (node (ref "CN5-1") (pin "17") (pinfunction "17_17") (pintype "unspecified"))
      (node (ref "CN5-2") (pin "17") (pinfunction "17_17") (pintype "unspecified"))
      (node (ref "U2-MASTER") (pin "3") (pinfunction "DCK_3") (pintype "unspecified"))
      (node (ref "U28") (pin "53") (pinfunction "PWM/SCK/D52_53") (pintype "unspecified"))
      (node (ref "U3-SLAVE") (pin "3") (pinfunction "DCK_3") (pintype "unspecified"))
    )
    (net (code "153") (name "SS") (class "Default")
      (node (ref "CN5-1") (pin "19") (pinfunction "19_19") (pintype "unspecified"))
      (node (ref "CN5-2") (pin "19") (pinfunction "19_19") (pintype "unspecified"))
    )
    (net (code "154") (name "U2") (class "Default")
      (node (ref "U2-MASTER") (pin "22") (pinfunction "DAO_22") (pintype "unspecified"))
      (node (ref "U3-SLAVE") (pin "2") (pinfunction "DAI_2") (pintype "unspecified"))
    )
    (net (code "155") (name "unconnected-(ALIM_EXTERNE_7.5V-Pad3)") (class "Default")
      (node (ref "ALIM_EXTERNE_7.5V") (pin "3") (pinfunction "3_3") (pintype "unspecified"))
    )
    (net (code "156") (name "unconnected-(R1-Pad1)") (class "Default")
      (node (ref "R1") (pin "1") (pinfunction "1_1") (pintype "unspecified"))
    )
    (net (code "157") (name "unconnected-(RN1-Pad7)") (class "Default")
      (node (ref "RN1") (pin "7") (pinfunction "7_7") (pintype "input"))
    )
    (net (code "158") (name "unconnected-(RN2-Pad6)") (class "Default")
      (node (ref "RN2") (pin "6") (pinfunction "6_6") (pintype "input"))
    )
    (net (code "159") (name "unconnected-(RN2-Pad7)") (class "Default")
      (node (ref "RN2") (pin "7") (pinfunction "7_7") (pintype "input"))
    )
    (net (code "160") (name "unconnected-(RN3-Pad7)") (class "Default")
      (node (ref "RN3") (pin "7") (pinfunction "7_7") (pintype "input"))
    )
    (net (code "161") (name "unconnected-(RN4-Pad2)") (class "Default")
      (node (ref "RN4") (pin "2") (pinfunction "2_2") (pintype "input"))
    )
    (net (code "162") (name "unconnected-(RN4-Pad3)") (class "Default")
      (node (ref "RN4") (pin "3") (pinfunction "3_3") (pintype "input"))
    )
    (net (code "163") (name "unconnected-(RN6-Pad2)") (class "Default")
      (node (ref "RN6") (pin "2") (pinfunction "2_2") (pintype "input"))
    )
    (net (code "164") (name "unconnected-(RN7-Pad7)") (class "Default")
      (node (ref "RN7") (pin "7") (pinfunction "7_7") (pintype "input"))
    )
    (net (code "165") (name "unconnected-(RN8-Pad7)") (class "Default")
      (node (ref "RN8") (pin "7") (pinfunction "7_7") (pintype "input"))
    )
    (net (code "166") (name "unconnected-(SW1-Pad2)") (class "Default")
      (node (ref "SW1") (pin "2") (pinfunction "2_2") (pintype "unspecified"))
    )
    (net (code "167") (name "unconnected-(SW1-Pad4)") (class "Default")
      (node (ref "SW1") (pin "4") (pinfunction "4_4") (pintype "unspecified"))
    )
    (net (code "168") (name "unconnected-(SW2-Pad2)") (class "Default")
      (node (ref "SW2") (pin "2") (pinfunction "2_2") (pintype "unspecified"))
    )
    (net (code "169") (name "unconnected-(SW2-Pad4)") (class "Default")
      (node (ref "SW2") (pin "4") (pinfunction "4_4") (pintype "unspecified"))
    )
    (net (code "170") (name "unconnected-(SW3-Pad2)") (class "Default")
      (node (ref "SW3") (pin "2") (pinfunction "2_2") (pintype "unspecified"))
    )
    (net (code "171") (name "unconnected-(SW3-Pad4)") (class "Default")
      (node (ref "SW3") (pin "4") (pinfunction "4_4") (pintype "unspecified"))
    )
    (net (code "172") (name "unconnected-(SW4-Pad2)") (class "Default")
      (node (ref "SW4") (pin "2") (pinfunction "2_2") (pintype "unspecified"))
    )
    (net (code "173") (name "unconnected-(SW4-Pad4)") (class "Default")
      (node (ref "SW4") (pin "4") (pinfunction "4_4") (pintype "unspecified"))
    )
    (net (code "174") (name "unconnected-(SW5-Pad2)") (class "Default")
      (node (ref "SW5") (pin "2") (pinfunction "2_2") (pintype "unspecified"))
    )
    (net (code "175") (name "unconnected-(SW5-Pad4)") (class "Default")
      (node (ref "SW5") (pin "4") (pinfunction "4_4") (pintype "unspecified"))
    )
    (net (code "176") (name "unconnected-(SW6-Pad2)") (class "Default")
      (node (ref "SW6") (pin "2") (pinfunction "2_2") (pintype "unspecified"))
    )
    (net (code "177") (name "unconnected-(SW6-Pad4)") (class "Default")
      (node (ref "SW6") (pin "4") (pinfunction "4_4") (pintype "unspecified"))
    )
    (net (code "178") (name "unconnected-(SW7-B{slash}W--Pad6)") (class "Default")
      (node (ref "SW7") (pin "6") (pinfunction "B/W-_6") (pintype "unspecified+no_connect"))
    )
    (net (code "179") (name "unconnected-(SW7-NC-Pad3)") (class "Default")
      (node (ref "SW7") (pin "3") (pinfunction "NC_3") (pintype "unspecified+no_connect"))
    )
    (net (code "180") (name "unconnected-(SW8-B{slash}W--Pad6)") (class "Default")
      (node (ref "SW8") (pin "6") (pinfunction "B/W-_6") (pintype "unspecified+no_connect"))
    )
    (net (code "181") (name "unconnected-(SW8-G--Pad7)") (class "Default")
      (node (ref "SW8") (pin "7") (pinfunction "G-_7") (pintype "unspecified+no_connect"))
    )
    (net (code "182") (name "unconnected-(SW8-NC-Pad3)") (class "Default")
      (node (ref "SW8") (pin "3") (pinfunction "NC_3") (pintype "unspecified+no_connect"))
    )
    (net (code "183") (name "unconnected-(SW9-Pad4)") (class "Default")
      (node (ref "SW9") (pin "4") (pinfunction "4_4") (pintype "unspecified"))
    )
    (net (code "184") (name "unconnected-(SW9-Pad5)") (class "Default")
      (node (ref "SW9") (pin "5") (pinfunction "5_5") (pintype "unspecified"))
    )
    (net (code "185") (name "unconnected-(SW9-Pad6)") (class "Default")
      (node (ref "SW9") (pin "6") (pinfunction "6_6") (pintype "unspecified"))
    )
    (net (code "186") (name "unconnected-(SW9-Pad7)") (class "Default")
      (node (ref "SW9") (pin "7") (pinfunction "7_7") (pintype "unspecified"))
    )
    (net (code "187") (name "unconnected-(U2-MASTER-OUT11-Pad16)") (class "Default")
      (node (ref "U2-MASTER") (pin "16") (pinfunction "OUT11_16") (pintype "unspecified"))
    )
    (net (code "188") (name "unconnected-(U2-MASTER-OUT13-Pad18)") (class "Default")
      (node (ref "U2-MASTER") (pin "18") (pinfunction "OUT13_18") (pintype "unspecified"))
    )
    (net (code "189") (name "unconnected-(U2-MASTER-OUT14-Pad19)") (class "Default")
      (node (ref "U2-MASTER") (pin "19") (pinfunction "OUT14_19") (pintype "unspecified"))
    )
    (net (code "190") (name "unconnected-(U2-MASTER-OUT15-Pad20)") (class "Default")
      (node (ref "U2-MASTER") (pin "20") (pinfunction "OUT15_20") (pintype "unspecified"))
    )
    (net (code "191") (name "unconnected-(U3-SLAVE-DAO-Pad22)") (class "Default")
      (node (ref "U3-SLAVE") (pin "22") (pinfunction "DAO_22") (pintype "unspecified"))
    )
    (net (code "192") (name "unconnected-(U3-SLAVE-OUT6-Pad11)") (class "Default")
      (node (ref "U3-SLAVE") (pin "11") (pinfunction "OUT6_11") (pintype "unspecified"))
    )
    (net (code "193") (name "unconnected-(U3-SLAVE-OUT10-Pad15)") (class "Default")
      (node (ref "U3-SLAVE") (pin "15") (pinfunction "OUT10_15") (pintype "unspecified"))
    )
    (net (code "194") (name "unconnected-(U3-SLAVE-OUT11-Pad16)") (class "Default")
      (node (ref "U3-SLAVE") (pin "16") (pinfunction "OUT11_16") (pintype "unspecified"))
    )
    (net (code "195") (name "unconnected-(U3-SLAVE-OUT12-Pad17)") (class "Default")
      (node (ref "U3-SLAVE") (pin "17") (pinfunction "OUT12_17") (pintype "unspecified"))
    )
    (net (code "196") (name "unconnected-(U3-SLAVE-OUT13-Pad18)") (class "Default")
      (node (ref "U3-SLAVE") (pin "18") (pinfunction "OUT13_18") (pintype "unspecified"))
    )
    (net (code "197") (name "unconnected-(U3-SLAVE-OUT14-Pad19)") (class "Default")
      (node (ref "U3-SLAVE") (pin "19") (pinfunction "OUT14_19") (pintype "unspecified"))
    )
    (net (code "198") (name "unconnected-(U3-SLAVE-OUT15-Pad20)") (class "Default")
      (node (ref "U3-SLAVE") (pin "20") (pinfunction "OUT15_20") (pintype "unspecified"))
    )
    (net (code "199") (name "unconnected-(U28-3V3-Pad78)") (class "Default")
      (node (ref "U28") (pin "78") (pinfunction "3V3_78") (pintype "unspecified+no_connect"))
    )
    (net (code "200") (name "unconnected-(U28-5V-Pad77)") (class "Default")
      (node (ref "U28") (pin "77") (pinfunction "5V_77") (pintype "unspecified"))
    )
    (net (code "201") (name "unconnected-(U28-A9-Pad64)") (class "Default")
      (node (ref "U28") (pin "64") (pinfunction "A9_64") (pintype "unspecified+no_connect"))
    )
    (net (code "202") (name "unconnected-(U28-A10-Pad65)") (class "Default")
      (node (ref "U28") (pin "65") (pinfunction "A10_65") (pintype "unspecified+no_connect"))
    )
    (net (code "203") (name "unconnected-(U28-A11-Pad66)") (class "Default")
      (node (ref "U28") (pin "66") (pinfunction "A11_66") (pintype "unspecified+no_connect"))
    )
    (net (code "204") (name "unconnected-(U28-A12-Pad67)") (class "Default")
      (node (ref "U28") (pin "67") (pinfunction "A12_67") (pintype "unspecified+no_connect"))
    )
    (net (code "205") (name "unconnected-(U28-A13-Pad68)") (class "Default")
      (node (ref "U28") (pin "68") (pinfunction "A13_68") (pintype "unspecified+no_connect"))
    )
    (net (code "206") (name "unconnected-(U28-A14-Pad69)") (class "Default")
      (node (ref "U28") (pin "69") (pinfunction "A14_69") (pintype "unspecified+no_connect"))
    )
    (net (code "207") (name "unconnected-(U28-A15-Pad70)") (class "Default")
      (node (ref "U28") (pin "70") (pinfunction "A15_70") (pintype "unspecified+no_connect"))
    )
    (net (code "208") (name "unconnected-(U28-AREF-Pad80)") (class "Default")
      (node (ref "U28") (pin "80") (pinfunction "AREF_80") (pintype "unspecified+no_connect"))
    )
    (net (code "209") (name "unconnected-(U28-D0{slash}Rx0-Pad1)") (class "Default")
      (node (ref "U28") (pin "1") (pinfunction "D0/Rx0_1") (pintype "unspecified+no_connect"))
    )
    (net (code "210") (name "unconnected-(U28-D1{slash}Tx0-Pad2)") (class "Default")
      (node (ref "U28") (pin "2") (pinfunction "D1/Tx0_2") (pintype "unspecified+no_connect"))
    )
    (net (code "211") (name "unconnected-(U28-RST-Pad81)") (class "Default")
      (node (ref "U28") (pin "81") (pinfunction "RST_81") (pintype "unspecified+no_connect"))
    )
    (net (code "212") (name "unconnected-(U28-VIN-Pad72)") (class "Default")
      (node (ref "U28") (pin "72") (pinfunction "VIN_72") (pintype "unspecified+no_connect"))
    )
  )
)
